# PowerSupplies.net
KiCad netlist of a schematic drawn in Altium Designer
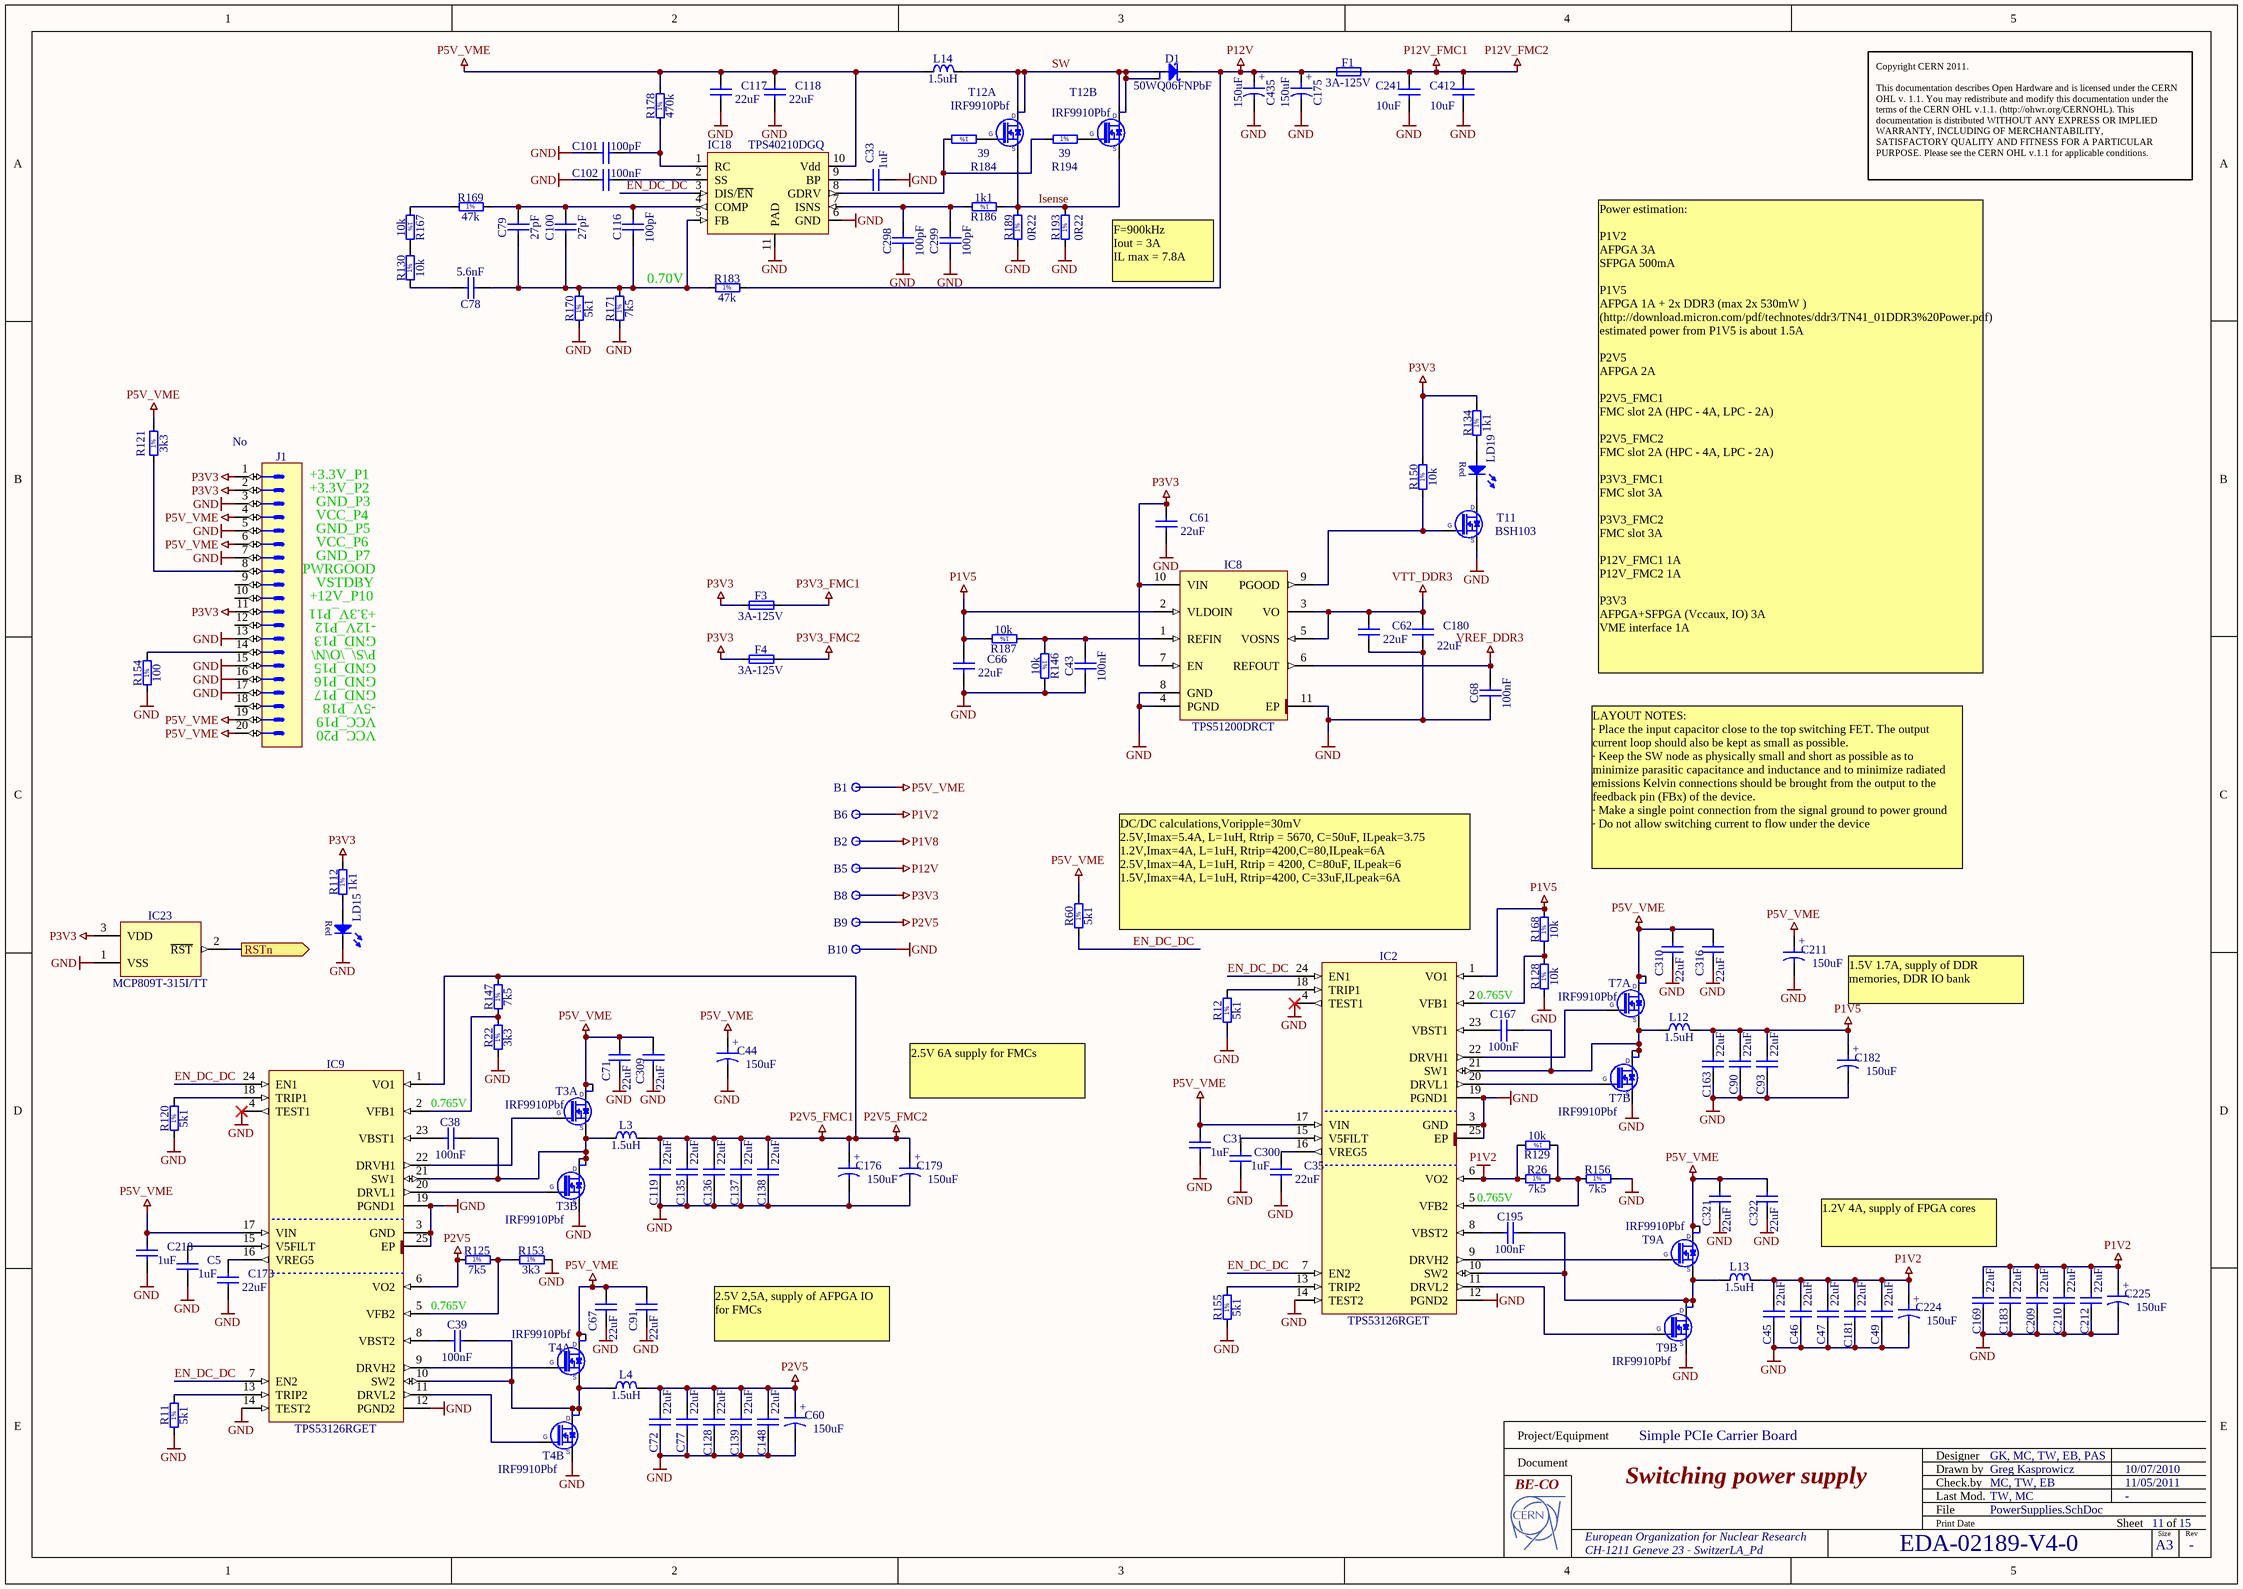
[diagram p0: PowerSupplies.SchDoc]

(export (version "E")
  (design (tool "Eeschema 10.0.6"))
  (components
    (comp (ref "B1")
      (value "Plated Hole")
      (footprint "c130h80")
      (description "Single Terminal Socket")
      (fields (field (name "PART NUMBER") "PLATED_HOLE0.8_PAD1.3") (field (name "AUTHOR") "CERN DEM JLC"))
      (libsource (lib "Eletro-mechanical") (part "Single Terminal Socket"))
    )
    (comp (ref "B2")
      (value "Plated Hole")
      (footprint "c130h80")
      (description "Single Terminal Socket")
      (fields (field (name "PART NUMBER") "PLATED_HOLE0.8_PAD1.3") (field (name "AUTHOR") "CERN DEM JLC"))
      (libsource (lib "Eletro-mechanical") (part "Single Terminal Socket"))
    )
    (comp (ref "B5")
      (value "Plated Hole")
      (footprint "c130h80")
      (description "Single Terminal Socket")
      (fields (field (name "PART NUMBER") "PLATED_HOLE0.8_PAD1.3") (field (name "AUTHOR") "CERN DEM JLC"))
      (libsource (lib "Eletro-mechanical") (part "Single Terminal Socket"))
    )
    (comp (ref "B6")
      (value "Plated Hole")
      (footprint "c130h80")
      (description "Single Terminal Socket")
      (fields (field (name "PART NUMBER") "PLATED_HOLE0.8_PAD1.3") (field (name "AUTHOR") "CERN DEM JLC"))
      (libsource (lib "Eletro-mechanical") (part "Single Terminal Socket"))
    )
    (comp (ref "B8")
      (value "Plated Hole")
      (footprint "c130h80")
      (description "Single Terminal Socket")
      (fields (field (name "PART NUMBER") "PLATED_HOLE0.8_PAD1.3") (field (name "AUTHOR") "CERN DEM JLC"))
      (libsource (lib "Eletro-mechanical") (part "Single Terminal Socket"))
    )
    (comp (ref "B9")
      (value "Plated Hole")
      (footprint "c130h80")
      (description "Single Terminal Socket")
      (fields (field (name "PART NUMBER") "PLATED_HOLE0.8_PAD1.3") (field (name "AUTHOR") "CERN DEM JLC"))
      (libsource (lib "Eletro-mechanical") (part "Single Terminal Socket"))
    )
    (comp (ref "B10")
      (value "Plated Hole")
      (footprint "c130h80")
      (description "Single Terminal Socket")
      (fields (field (name "PART NUMBER") "PLATED_HOLE0.8_PAD1.3") (field (name "AUTHOR") "CERN DEM JLC"))
      (libsource (lib "Eletro-mechanical") (part "Single Terminal Socket"))
    )
    (comp (ref "C5")
      (value "1uF")
      (footprint "CAPC1608X87N")
      (description "Non-polarised capacitor")
      (fields
        (field (name "PART NUMBER") "CC0603_1UF_16V_10%_X7R")
        (field (name "VOLTAGE") "16V")
        (field (name "AUTHOR") "CERN DEM JLC")
      )
      (libsource (lib "Capacitors") (part "Capacitor - non polarized"))
    )
    (comp (ref "C31")
      (value "1uF")
      (footprint "CAPC1608X87N")
      (description "Non-polarised capacitor")
      (fields
        (field (name "PART NUMBER") "CC0603_1UF_16V_10%_X7R")
        (field (name "VOLTAGE") "16V")
        (field (name "AUTHOR") "CERN DEM JLC")
      )
      (libsource (lib "Capacitors") (part "Capacitor - non polarized"))
    )
    (comp (ref "C33")
      (value "1uF")
      (footprint "CAPC1608X87N")
      (description "Non-polarised capacitor")
      (fields
        (field (name "PART NUMBER") "CC0603_1UF_16V_10%_X7R")
        (field (name "VOLTAGE") "16V")
        (field (name "AUTHOR") "CERN DEM JLC")
      )
      (libsource (lib "Capacitors") (part "Capacitor - non polarized"))
    )
    (comp (ref "C35")
      (value "22uF")
      (footprint "CAPC3216X180N")
      (description "Non-polarised capacitor")
      (fields
        (field (name "PART NUMBER") "CC1206_22UF_10V_10%_X7R")
        (field (name "VOLTAGE") "10V")
        (field (name "AUTHOR") "CERN DEM JLC")
      )
      (libsource (lib "Capacitors") (part "Capacitor - non polarized"))
    )
    (comp (ref "C38")
      (value "100nF")
      (footprint "CAPC1005X55N")
      (description "Non-polarised capacitor")
      (fields
        (field (name "PART NUMBER") "CC0402_100NF_16V_10%_X7R")
        (field (name "VOLTAGE") "16V")
        (field (name "AUTHOR") "CERN DEM JLC")
      )
      (libsource (lib "Capacitors") (part "Capacitor - non polarized"))
    )
    (comp (ref "C39")
      (value "100nF")
      (footprint "CAPC1005X55N")
      (description "Non-polarised capacitor")
      (fields
        (field (name "PART NUMBER") "CC0402_100NF_16V_10%_X7R")
        (field (name "VOLTAGE") "16V")
        (field (name "AUTHOR") "CERN DEM JLC")
      )
      (libsource (lib "Capacitors") (part "Capacitor - non polarized"))
    )
    (comp (ref "C43")
      (value "100nF")
      (footprint "CAPC1005X55N")
      (description "Non-polarised capacitor")
      (fields
        (field (name "PART NUMBER") "CC0402_100NF_16V_10%_X7R")
        (field (name "VOLTAGE") "16V")
        (field (name "AUTHOR") "CERN DEM JLC")
      )
      (libsource (lib "Capacitors") (part "Capacitor - non polarized"))
    )
    (comp (ref "C44")
      (value "150uF")
      (footprint "CAPPR350-850X700")
      (description "Polarised capacitor")
      (fields
        (field (name "PART NUMBER") "CAER_150UF_6.3V_20%_SANYO_6SEQP150M")
        (field (name "VOLTAGE") "6.3V")
        (field (name "AUTHOR") "CERN DEM JLC")
      )
      (libsource (lib "Capacitors") (part "Capacitor - polarized"))
    )
    (comp (ref "C45")
      (value "22uF")
      (footprint "CAPC3216X180N")
      (description "Non-polarised capacitor")
      (fields
        (field (name "PART NUMBER") "CC1206_22UF_10V_10%_X7R")
        (field (name "VOLTAGE") "10V")
        (field (name "AUTHOR") "CERN DEM JLC")
      )
      (libsource (lib "Capacitors") (part "Capacitor - non polarized"))
    )
    (comp (ref "C46")
      (value "22uF")
      (footprint "CAPC3216X180N")
      (description "Non-polarised capacitor")
      (fields
        (field (name "PART NUMBER") "CC1206_22UF_10V_10%_X7R")
        (field (name "VOLTAGE") "10V")
        (field (name "AUTHOR") "CERN DEM JLC")
      )
      (libsource (lib "Capacitors") (part "Capacitor - non polarized"))
    )
    (comp (ref "C47")
      (value "22uF")
      (footprint "CAPC3216X180N")
      (description "Non-polarised capacitor")
      (fields
        (field (name "PART NUMBER") "CC1206_22UF_10V_10%_X7R")
        (field (name "VOLTAGE") "10V")
        (field (name "AUTHOR") "CERN DEM JLC")
      )
      (libsource (lib "Capacitors") (part "Capacitor - non polarized"))
    )
    (comp (ref "C49")
      (value "22uF")
      (footprint "CAPC3216X180N")
      (description "Non-polarised capacitor")
      (fields
        (field (name "PART NUMBER") "CC1206_22UF_10V_10%_X7R")
        (field (name "VOLTAGE") "10V")
        (field (name "AUTHOR") "CERN DEM JLC")
      )
      (libsource (lib "Capacitors") (part "Capacitor - non polarized"))
    )
    (comp (ref "C60")
      (value "150uF")
      (footprint "CAPPR350-850X700")
      (description "Polarised capacitor")
      (fields
        (field (name "PART NUMBER") "CAER_150UF_6.3V_20%_SANYO_6SEQP150M")
        (field (name "VOLTAGE") "6.3V")
        (field (name "AUTHOR") "CERN DEM JLC")
      )
      (libsource (lib "Capacitors") (part "Capacitor - polarized"))
    )
    (comp (ref "C61")
      (value "22uF")
      (footprint "CAPC3216X180N")
      (description "Non-polarised capacitor")
      (fields
        (field (name "PART NUMBER") "CC1206_22UF_10V_10%_X7R")
        (field (name "VOLTAGE") "10V")
        (field (name "AUTHOR") "CERN DEM JLC")
      )
      (libsource (lib "Capacitors") (part "Capacitor - non polarized"))
    )
    (comp (ref "C62")
      (value "22uF")
      (footprint "CAPC3216X180N")
      (description "Non-polarised capacitor")
      (fields
        (field (name "PART NUMBER") "CC1206_22UF_10V_10%_X7R")
        (field (name "VOLTAGE") "10V")
        (field (name "AUTHOR") "CERN DEM JLC")
      )
      (libsource (lib "Capacitors") (part "Capacitor - non polarized"))
    )
    (comp (ref "C66")
      (value "22uF")
      (footprint "CAPC3216X180N")
      (description "Non-polarised capacitor")
      (fields
        (field (name "PART NUMBER") "CC1206_22UF_10V_10%_X7R")
        (field (name "VOLTAGE") "10V")
        (field (name "AUTHOR") "CERN DEM JLC")
      )
      (libsource (lib "Capacitors") (part "Capacitor - non polarized"))
    )
    (comp (ref "C67")
      (value "22uF")
      (footprint "CAPC3216X180N")
      (description "Non-polarised capacitor")
      (fields
        (field (name "PART NUMBER") "CC1206_22UF_10V_10%_X7R")
        (field (name "VOLTAGE") "10V")
        (field (name "AUTHOR") "CERN DEM JLC")
      )
      (libsource (lib "Capacitors") (part "Capacitor - non polarized"))
    )
    (comp (ref "C68")
      (value "100nF")
      (footprint "CAPC1005X55N")
      (description "Non-polarised capacitor")
      (fields
        (field (name "PART NUMBER") "CC0402_100NF_16V_10%_X7R")
        (field (name "VOLTAGE") "16V")
        (field (name "AUTHOR") "CERN DEM JLC")
      )
      (libsource (lib "Capacitors") (part "Capacitor - non polarized"))
    )
    (comp (ref "C71")
      (value "22uF")
      (footprint "CAPC3216X180N")
      (description "Non-polarised capacitor")
      (fields
        (field (name "PART NUMBER") "CC1206_22UF_10V_10%_X7R")
        (field (name "VOLTAGE") "10V")
        (field (name "AUTHOR") "CERN DEM JLC")
      )
      (libsource (lib "Capacitors") (part "Capacitor - non polarized"))
    )
    (comp (ref "C72")
      (value "22uF")
      (footprint "CAPC3216X180N")
      (description "Non-polarised capacitor")
      (fields
        (field (name "PART NUMBER") "CC1206_22UF_10V_10%_X7R")
        (field (name "VOLTAGE") "10V")
        (field (name "AUTHOR") "CERN DEM JLC")
      )
      (libsource (lib "Capacitors") (part "Capacitor - non polarized"))
    )
    (comp (ref "C77")
      (value "22uF")
      (footprint "CAPC3216X180N")
      (description "Non-polarised capacitor")
      (fields
        (field (name "PART NUMBER") "CC1206_22UF_10V_10%_X7R")
        (field (name "VOLTAGE") "10V")
        (field (name "AUTHOR") "CERN DEM JLC")
      )
      (libsource (lib "Capacitors") (part "Capacitor - non polarized"))
    )
    (comp (ref "C78")
      (value "5.6nF")
      (footprint "CAPC1608X87N")
      (description "Non-polarised capacitor")
      (fields
        (field (name "PART NUMBER") "CC0603_5.6NF_50V_5%_X7R")
        (field (name "VOLTAGE") "50V")
        (field (name "AUTHOR") "CERN DEM JLC")
      )
      (libsource (lib "Capacitors") (part "Capacitor - non polarized"))
    )
    (comp (ref "C79")
      (value "27pF")
      (footprint "CAPC1608X87N")
      (description "Non-polarised capacitor")
      (fields
        (field (name "PART NUMBER") "CC0603_27PF_50V_5%_NP0")
        (field (name "VOLTAGE") "50V")
        (field (name "AUTHOR") "CERN DEM JLC")
      )
      (libsource (lib "Capacitors") (part "Capacitor - non polarized"))
    )
    (comp (ref "C90")
      (value "22uF")
      (footprint "CAPC3216X180N")
      (description "Non-polarised capacitor")
      (fields
        (field (name "PART NUMBER") "CC1206_22UF_10V_10%_X7R")
        (field (name "VOLTAGE") "10V")
        (field (name "AUTHOR") "CERN DEM JLC")
      )
      (libsource (lib "Capacitors") (part "Capacitor - non polarized"))
    )
    (comp (ref "C91")
      (value "22uF")
      (footprint "CAPC3216X180N")
      (description "Non-polarised capacitor")
      (fields
        (field (name "PART NUMBER") "CC1206_22UF_10V_10%_X7R")
        (field (name "VOLTAGE") "10V")
        (field (name "AUTHOR") "CERN DEM JLC")
      )
      (libsource (lib "Capacitors") (part "Capacitor - non polarized"))
    )
    (comp (ref "C93")
      (value "22uF")
      (footprint "CAPC3216X180N")
      (description "Non-polarised capacitor")
      (fields
        (field (name "PART NUMBER") "CC1206_22UF_10V_10%_X7R")
        (field (name "VOLTAGE") "10V")
        (field (name "AUTHOR") "CERN DEM JLC")
      )
      (libsource (lib "Capacitors") (part "Capacitor - non polarized"))
    )
    (comp (ref "C100")
      (value "27pF")
      (footprint "CAPC1608X87N")
      (description "Non-polarised capacitor")
      (fields
        (field (name "PART NUMBER") "CC0603_27PF_50V_5%_NP0")
        (field (name "VOLTAGE") "50V")
        (field (name "AUTHOR") "CERN DEM JLC")
      )
      (libsource (lib "Capacitors") (part "Capacitor - non polarized"))
    )
    (comp (ref "C101")
      (value "100pF")
      (footprint "CAPC1608X87N")
      (description "Non-polarised capacitor")
      (fields
        (field (name "PART NUMBER") "CC0603_100PF_50V_5%_NP0")
        (field (name "VOLTAGE") "50V")
        (field (name "AUTHOR") "CERN DEM JLC")
      )
      (libsource (lib "Capacitors") (part "Capacitor - non polarized"))
    )
    (comp (ref "C102")
      (value "100nF")
      (footprint "CAPC1005X55N")
      (description "Non-polarised capacitor")
      (fields
        (field (name "PART NUMBER") "CC0402_100NF_16V_10%_X7R")
        (field (name "VOLTAGE") "16V")
        (field (name "AUTHOR") "CERN DEM JLC")
      )
      (libsource (lib "Capacitors") (part "Capacitor - non polarized"))
    )
    (comp (ref "C116")
      (value "100pF")
      (footprint "CAPC1608X87N")
      (description "Non-polarised capacitor")
      (fields
        (field (name "PART NUMBER") "CC0603_100PF_50V_5%_NP0")
        (field (name "VOLTAGE") "50V")
        (field (name "AUTHOR") "CERN DEM JLC")
      )
      (libsource (lib "Capacitors") (part "Capacitor - non polarized"))
    )
    (comp (ref "C117")
      (value "22uF")
      (footprint "CAPC3216X180N")
      (description "Non-polarised capacitor")
      (fields
        (field (name "PART NUMBER") "CC1206_22UF_10V_10%_X7R")
        (field (name "VOLTAGE") "10V")
        (field (name "AUTHOR") "CERN DEM JLC")
      )
      (libsource (lib "Capacitors") (part "Capacitor - non polarized"))
    )
    (comp (ref "C118")
      (value "22uF")
      (footprint "CAPC3216X180N")
      (description "Non-polarised capacitor")
      (fields
        (field (name "PART NUMBER") "CC1206_22UF_10V_10%_X7R")
        (field (name "VOLTAGE") "10V")
        (field (name "AUTHOR") "CERN DEM JLC")
      )
      (libsource (lib "Capacitors") (part "Capacitor - non polarized"))
    )
    (comp (ref "C119")
      (value "22uF")
      (footprint "CAPC3216X180N")
      (description "Non-polarised capacitor")
      (fields
        (field (name "PART NUMBER") "CC1206_22UF_10V_10%_X7R")
        (field (name "VOLTAGE") "10V")
        (field (name "AUTHOR") "CERN DEM JLC")
      )
      (libsource (lib "Capacitors") (part "Capacitor - non polarized"))
    )
    (comp (ref "C128")
      (value "22uF")
      (footprint "CAPC3216X180N")
      (description "Non-polarised capacitor")
      (fields
        (field (name "PART NUMBER") "CC1206_22UF_10V_10%_X7R")
        (field (name "VOLTAGE") "10V")
        (field (name "AUTHOR") "CERN DEM JLC")
      )
      (libsource (lib "Capacitors") (part "Capacitor - non polarized"))
    )
    (comp (ref "C135")
      (value "22uF")
      (footprint "CAPC3216X180N")
      (description "Non-polarised capacitor")
      (fields
        (field (name "PART NUMBER") "CC1206_22UF_10V_10%_X7R")
        (field (name "VOLTAGE") "10V")
        (field (name "AUTHOR") "CERN DEM JLC")
      )
      (libsource (lib "Capacitors") (part "Capacitor - non polarized"))
    )
    (comp (ref "C136")
      (value "22uF")
      (footprint "CAPC3216X180N")
      (description "Non-polarised capacitor")
      (fields
        (field (name "PART NUMBER") "CC1206_22UF_10V_10%_X7R")
        (field (name "VOLTAGE") "10V")
        (field (name "AUTHOR") "CERN DEM JLC")
      )
      (libsource (lib "Capacitors") (part "Capacitor - non polarized"))
    )
    (comp (ref "C137")
      (value "22uF")
      (footprint "CAPC3216X180N")
      (description "Non-polarised capacitor")
      (fields
        (field (name "PART NUMBER") "CC1206_22UF_10V_10%_X7R")
        (field (name "VOLTAGE") "10V")
        (field (name "AUTHOR") "CERN DEM JLC")
      )
      (libsource (lib "Capacitors") (part "Capacitor - non polarized"))
    )
    (comp (ref "C138")
      (value "22uF")
      (footprint "CAPC3216X180N")
      (description "Non-polarised capacitor")
      (fields
        (field (name "PART NUMBER") "CC1206_22UF_10V_10%_X7R")
        (field (name "VOLTAGE") "10V")
        (field (name "AUTHOR") "CERN DEM JLC")
      )
      (libsource (lib "Capacitors") (part "Capacitor - non polarized"))
    )
    (comp (ref "C139")
      (value "22uF")
      (footprint "CAPC3216X180N")
      (description "Non-polarised capacitor")
      (fields
        (field (name "PART NUMBER") "CC1206_22UF_10V_10%_X7R")
        (field (name "VOLTAGE") "10V")
        (field (name "AUTHOR") "CERN DEM JLC")
      )
      (libsource (lib "Capacitors") (part "Capacitor - non polarized"))
    )
    (comp (ref "C148")
      (value "22uF")
      (footprint "CAPC3216X180N")
      (description "Non-polarised capacitor")
      (fields
        (field (name "PART NUMBER") "CC1206_22UF_10V_10%_X7R")
        (field (name "VOLTAGE") "10V")
        (field (name "AUTHOR") "CERN DEM JLC")
      )
      (libsource (lib "Capacitors") (part "Capacitor - non polarized"))
    )
    (comp (ref "C163")
      (value "22uF")
      (footprint "CAPC3216X180N")
      (description "Non-polarised capacitor")
      (fields
        (field (name "PART NUMBER") "CC1206_22UF_10V_10%_X7R")
        (field (name "VOLTAGE") "10V")
        (field (name "AUTHOR") "CERN DEM JLC")
      )
      (libsource (lib "Capacitors") (part "Capacitor - non polarized"))
    )
    (comp (ref "C167")
      (value "100nF")
      (footprint "CAPC1005X55N")
      (description "Non-polarised capacitor")
      (fields
        (field (name "PART NUMBER") "CC0402_100NF_16V_10%_X7R")
        (field (name "VOLTAGE") "16V")
        (field (name "AUTHOR") "CERN DEM JLC")
      )
      (libsource (lib "Capacitors") (part "Capacitor - non polarized"))
    )
    (comp (ref "C169")
      (value "22uF")
      (footprint "CAPC3216X180N")
      (description "Non-polarised capacitor")
      (fields
        (field (name "PART NUMBER") "CC1206_22UF_10V_10%_X7R")
        (field (name "VOLTAGE") "10V")
        (field (name "AUTHOR") "CERN DEM JLC")
      )
      (libsource (lib "Capacitors") (part "Capacitor - non polarized"))
    )
    (comp (ref "C173")
      (value "22uF")
      (footprint "CAPC3216X180N")
      (description "Non-polarised capacitor")
      (fields
        (field (name "PART NUMBER") "CC1206_22UF_10V_10%_X7R")
        (field (name "VOLTAGE") "10V")
        (field (name "AUTHOR") "CERN DEM JLC")
      )
      (libsource (lib "Capacitors") (part "Capacitor - non polarized"))
    )
    (comp (ref "C175")
      (value "150uF")
      (footprint "CAPPR500-1050X800")
      (description "Polarised capacitor")
      (fields
        (field (name "PART NUMBER") "CAER_150UF_16V_20%_SANYO_16SEQP150M")
        (field (name "VOLTAGE") "16V")
        (field (name "AUTHOR") "CERN DEM JLC")
      )
      (libsource (lib "Capacitors") (part "Capacitor - polarized"))
    )
    (comp (ref "C176")
      (value "150uF")
      (footprint "CAPPR350-850X700")
      (description "Polarised capacitor")
      (fields
        (field (name "PART NUMBER") "CAER_150UF_6.3V_20%_SANYO_6SEQP150M")
        (field (name "VOLTAGE") "6.3V")
        (field (name "AUTHOR") "CERN DEM JLC")
      )
      (libsource (lib "Capacitors") (part "Capacitor - polarized"))
    )
    (comp (ref "C179")
      (value "150uF")
      (footprint "CAPPR350-850X700")
      (description "Polarised capacitor")
      (fields
        (field (name "PART NUMBER") "CAER_150UF_6.3V_20%_SANYO_6SEQP150M")
        (field (name "VOLTAGE") "6.3V")
        (field (name "AUTHOR") "CERN DEM JLC")
      )
      (libsource (lib "Capacitors") (part "Capacitor - polarized"))
    )
    (comp (ref "C180")
      (value "22uF")
      (footprint "CAPC3216X180N")
      (description "Non-polarised capacitor")
      (fields
        (field (name "PART NUMBER") "CC1206_22UF_10V_10%_X7R")
        (field (name "VOLTAGE") "10V")
        (field (name "AUTHOR") "CERN DEM JLC")
      )
      (libsource (lib "Capacitors") (part "Capacitor - non polarized"))
    )
    (comp (ref "C181")
      (value "22uF")
      (footprint "CAPC3216X180N")
      (description "Non-polarised capacitor")
      (fields
        (field (name "PART NUMBER") "CC1206_22UF_10V_10%_X7R")
        (field (name "VOLTAGE") "10V")
        (field (name "AUTHOR") "CERN DEM JLC")
      )
      (libsource (lib "Capacitors") (part "Capacitor - non polarized"))
    )
    (comp (ref "C182")
      (value "150uF")
      (footprint "CAPPR350-850X700")
      (description "Polarised capacitor")
      (fields
        (field (name "PART NUMBER") "CAER_150UF_6.3V_20%_SANYO_6SEQP150M")
        (field (name "VOLTAGE") "6.3V")
        (field (name "AUTHOR") "CERN DEM JLC")
      )
      (libsource (lib "Capacitors") (part "Capacitor - polarized"))
    )
    (comp (ref "C183")
      (value "22uF")
      (footprint "CAPC3216X180N")
      (description "Non-polarised capacitor")
      (fields
        (field (name "PART NUMBER") "CC1206_22UF_10V_10%_X7R")
        (field (name "VOLTAGE") "10V")
        (field (name "AUTHOR") "CERN DEM JLC")
      )
      (libsource (lib "Capacitors") (part "Capacitor - non polarized"))
    )
    (comp (ref "C195")
      (value "100nF")
      (footprint "CAPC1005X55N")
      (description "Non-polarised capacitor")
      (fields
        (field (name "PART NUMBER") "CC0402_100NF_16V_10%_X7R")
        (field (name "VOLTAGE") "16V")
        (field (name "AUTHOR") "CERN DEM JLC")
      )
      (libsource (lib "Capacitors") (part "Capacitor - non polarized"))
    )
    (comp (ref "C209")
      (value "22uF")
      (footprint "CAPC3216X180N")
      (description "Non-polarised capacitor")
      (fields
        (field (name "PART NUMBER") "CC1206_22UF_10V_10%_X7R")
        (field (name "VOLTAGE") "10V")
        (field (name "AUTHOR") "CERN DEM JLC")
      )
      (libsource (lib "Capacitors") (part "Capacitor - non polarized"))
    )
    (comp (ref "C210")
      (value "22uF")
      (footprint "CAPC3216X180N")
      (description "Non-polarised capacitor")
      (fields
        (field (name "PART NUMBER") "CC1206_22UF_10V_10%_X7R")
        (field (name "VOLTAGE") "10V")
        (field (name "AUTHOR") "CERN DEM JLC")
      )
      (libsource (lib "Capacitors") (part "Capacitor - non polarized"))
    )
    (comp (ref "C211")
      (value "150uF")
      (footprint "CAPPR350-850X700")
      (description "Polarised capacitor")
      (fields
        (field (name "PART NUMBER") "CAER_150UF_6.3V_20%_SANYO_6SEQP150M")
        (field (name "VOLTAGE") "6.3V")
        (field (name "AUTHOR") "CERN DEM JLC")
      )
      (libsource (lib "Capacitors") (part "Capacitor - polarized"))
    )
    (comp (ref "C212")
      (value "22uF")
      (footprint "CAPC3216X180N")
      (description "Non-polarised capacitor")
      (fields
        (field (name "PART NUMBER") "CC1206_22UF_10V_10%_X7R")
        (field (name "VOLTAGE") "10V")
        (field (name "AUTHOR") "CERN DEM JLC")
      )
      (libsource (lib "Capacitors") (part "Capacitor - non polarized"))
    )
    (comp (ref "C218")
      (value "1uF")
      (footprint "CAPC1608X87N")
      (description "Non-polarised capacitor")
      (fields
        (field (name "PART NUMBER") "CC0603_1UF_16V_10%_X7R")
        (field (name "VOLTAGE") "16V")
        (field (name "AUTHOR") "CERN DEM JLC")
      )
      (libsource (lib "Capacitors") (part "Capacitor - non polarized"))
    )
    (comp (ref "C224")
      (value "150uF")
      (footprint "CAPPR350-850X700")
      (description "Polarised capacitor")
      (fields
        (field (name "PART NUMBER") "CAER_150UF_6.3V_20%_SANYO_6SEQP150M")
        (field (name "VOLTAGE") "6.3V")
        (field (name "AUTHOR") "CERN DEM JLC")
      )
      (libsource (lib "Capacitors") (part "Capacitor - polarized"))
    )
    (comp (ref "C225")
      (value "150uF")
      (footprint "CAPPR350-850X700")
      (description "Polarised capacitor")
      (fields
        (field (name "PART NUMBER") "CAER_150UF_6.3V_20%_SANYO_6SEQP150M")
        (field (name "VOLTAGE") "6.3V")
        (field (name "AUTHOR") "CERN DEM JLC")
      )
      (libsource (lib "Capacitors") (part "Capacitor - polarized"))
    )
    (comp (ref "C241")
      (value "10uF")
      (footprint "CAPC3225X270N")
      (description "Non-polarised capacitor")
      (fields
        (field (name "PART NUMBER") "CC1210_10UF_25V_10%_X7R")
        (field (name "VOLTAGE") "25V")
        (field (name "AUTHOR") "CERN DEM JLC")
      )
      (libsource (lib "Capacitors") (part "Capacitor - non polarized"))
    )
    (comp (ref "C298")
      (value "100pF")
      (footprint "CAPC1608X87N")
      (description "Non-polarised capacitor")
      (fields
        (field (name "PART NUMBER") "CC0603_100PF_50V_5%_NP0")
        (field (name "VOLTAGE") "50V")
        (field (name "AUTHOR") "CERN DEM JLC")
      )
      (libsource (lib "Capacitors") (part "Capacitor - non polarized"))
    )
    (comp (ref "C299")
      (value "100pF")
      (footprint "CAPC1608X87N")
      (description "Non-polarised capacitor")
      (fields
        (field (name "PART NUMBER") "CC0603_100PF_50V_5%_NP0")
        (field (name "VOLTAGE") "50V")
        (field (name "AUTHOR") "CERN DEM JLC")
      )
      (libsource (lib "Capacitors") (part "Capacitor - non polarized"))
    )
    (comp (ref "C300")
      (value "1uF")
      (footprint "CAPC1608X87N")
      (description "Non-polarised capacitor")
      (fields
        (field (name "PART NUMBER") "CC0603_1UF_16V_10%_X7R")
        (field (name "VOLTAGE") "16V")
        (field (name "AUTHOR") "CERN DEM JLC")
      )
      (libsource (lib "Capacitors") (part "Capacitor - non polarized"))
    )
    (comp (ref "C309")
      (value "22uF")
      (footprint "CAPC3216X180N")
      (description "Non-polarised capacitor")
      (fields
        (field (name "PART NUMBER") "CC1206_22UF_10V_10%_X7R")
        (field (name "VOLTAGE") "10V")
        (field (name "AUTHOR") "CERN DEM JLC")
      )
      (libsource (lib "Capacitors") (part "Capacitor - non polarized"))
    )
    (comp (ref "C310")
      (value "22uF")
      (footprint "CAPC3216X180N")
      (description "Non-polarised capacitor")
      (fields
        (field (name "PART NUMBER") "CC1206_22UF_10V_10%_X7R")
        (field (name "VOLTAGE") "10V")
        (field (name "AUTHOR") "CERN DEM JLC")
      )
      (libsource (lib "Capacitors") (part "Capacitor - non polarized"))
    )
    (comp (ref "C316")
      (value "22uF")
      (footprint "CAPC3216X180N")
      (description "Non-polarised capacitor")
      (fields
        (field (name "PART NUMBER") "CC1206_22UF_10V_10%_X7R")
        (field (name "VOLTAGE") "10V")
        (field (name "AUTHOR") "CERN DEM JLC")
      )
      (libsource (lib "Capacitors") (part "Capacitor - non polarized"))
    )
    (comp (ref "C321")
      (value "22uF")
      (footprint "CAPC3216X180N")
      (description "Non-polarised capacitor")
      (fields
        (field (name "PART NUMBER") "CC1206_22UF_10V_10%_X7R")
        (field (name "VOLTAGE") "10V")
        (field (name "AUTHOR") "CERN DEM JLC")
      )
      (libsource (lib "Capacitors") (part "Capacitor - non polarized"))
    )
    (comp (ref "C322")
      (value "22uF")
      (footprint "CAPC3216X180N")
      (description "Non-polarised capacitor")
      (fields
        (field (name "PART NUMBER") "CC1206_22UF_10V_10%_X7R")
        (field (name "VOLTAGE") "10V")
        (field (name "AUTHOR") "CERN DEM JLC")
      )
      (libsource (lib "Capacitors") (part "Capacitor - non polarized"))
    )
    (comp (ref "C412")
      (value "10uF")
      (footprint "CAPC3225X270N")
      (description "Non-polarised capacitor")
      (fields
        (field (name "PART NUMBER") "CC1210_10UF_25V_10%_X7R")
        (field (name "VOLTAGE") "25V")
        (field (name "AUTHOR") "CERN DEM JLC")
      )
      (libsource (lib "Capacitors") (part "Capacitor - non polarized"))
    )
    (comp (ref "C435")
      (value "150uF")
      (footprint "CAPPR500-1050X800")
      (description "Polarised capacitor")
      (fields
        (field (name "PART NUMBER") "CAER_150UF_16V_20%_SANYO_16SEQP150M")
        (field (name "VOLTAGE") "16V")
        (field (name "AUTHOR") "CERN DEM JLC")
      )
      (libsource (lib "Capacitors") (part "Capacitor - polarized"))
    )
    (comp (ref "D1")
      (value "50WQ06FNPbF")
      (footprint "TO228P991X239-3N-R546X521")
      (description "Diode  Schottky Anode pin 1 and 2 cathode pin 3")
      (fields
        (field (name "VOLTAGE") "60V")
        (field (name "POWER") "5.5A")
        (field (name "AUTHOR") "CERN DEM JLC")
      )
      (libsource (lib "ICs And Semiconductors") (part "Diode Schottky A1A2_C3"))
    )
    (comp (ref "F1")
      (value "3A-125V")
      (footprint "FUSE_LITTELFUSE_0154")
      (description "Fuse")
      (fields
        (field (name "PART NUMBER") "FUSE_LITTELFUSE_0154003.DR")
        (field (name "MANUFACTURER") "LITTELFUSE")
        (field (name "AUTHOR") "CERN DEM JMW")
      )
      (libsource (lib "Eletro-mechanical") (part "Fuse"))
    )
    (comp (ref "F3")
      (value "3A-125V")
      (footprint "FUSE_LITTELFUSE_0154")
      (description "Fuse")
      (fields
        (field (name "PART NUMBER") "FUSE_LITTELFUSE_0154003.DR")
        (field (name "MANUFACTURER") "LITTELFUSE")
        (field (name "AUTHOR") "CERN DEM JMW")
      )
      (libsource (lib "Eletro-mechanical") (part "Fuse"))
    )
    (comp (ref "F4")
      (value "3A-125V")
      (footprint "FUSE_LITTELFUSE_0154")
      (description "Fuse")
      (fields
        (field (name "PART NUMBER") "FUSE_LITTELFUSE_0154003.DR")
        (field (name "MANUFACTURER") "LITTELFUSE")
        (field (name "AUTHOR") "CERN DEM JMW")
      )
      (libsource (lib "Eletro-mechanical") (part "Fuse"))
    )
    (comp (ref "IC2")
      (value "TPS53126RGET")
      (footprint "QFN50P400X400X100-25N-S255")
      (description "Dual Synchronous Step-Down Controller For Low Voltage Power Rails")
      (fields (field (name "MANUFACTURER") "TEXAS INSTRUMENTS") (field (name "AUTHOR") "CERN DEM JLC"))
      (libsource (lib "ICs And Semiconductors") (part "TPS53126RGET"))
    )
    (comp (ref "IC8")
      (value "TPS51200DRCT")
      (footprint "SON50P300X300X100-11N-R175X250")
      (description "Sink/Source DDR Termination Regulator")
      (fields (field (name "MANUFACTURER") "TEXAS INSTRUMENTS") (field (name "AUTHOR") "CERN DEM JLC"))
      (libsource (lib "ICs And Semiconductors") (part "TPS51200DRC"))
    )
    (comp (ref "IC9")
      (value "TPS53126RGET")
      (footprint "QFN50P400X400X100-25N-S255")
      (description "Dual Synchronous Step-Down Controller For Low Voltage Power Rails")
      (fields (field (name "MANUFACTURER") "TEXAS INSTRUMENTS") (field (name "AUTHOR") "CERN DEM JLC"))
      (libsource (lib "ICs And Semiconductors") (part "TPS53126RGET"))
    )
    (comp (ref "IC18")
      (value "TPS40210DGQ")
      (footprint "MSOP10_thermal")
      (description "4.5-V TO 52-V CURRENT MODE BOOST CONTROLLER")
      (libsource (lib "LIBRARY_SCH") (part "PM_TPS40210"))
    )
    (comp (ref "IC23")
      (value "MCP809T-315I/TT")
      (footprint "SOT95P237X112-3N")
      (description "3.075V Microcontroller Supervisory Circuit With Push-Pull Output")
      (fields (field (name "MANUFACTURER") "MICROCHIP TECHNOLOGY") (field (name "AUTHOR") "CERN DEM JLC"))
      (libsource (lib "ICs And Semiconductors") (part "MCP809"))
    )
    (comp (ref "J1")
      (value "Mini-Fit Jr.™")
      (footprint "MOLEX_39-28-1203")
      (description "Connector 20 Male")
      (fields
        (field (name "PART NUMBER") "MOLEX_39-28-1203")
        (field (name "MOUNTED") "No")
        (field (name "MANUFACTURER") "MOLEX")
        (field (name "AUTHOR") "CERN DEM JLC")
      )
      (libsource (lib "Connectors") (part "Connector 20 Male"))
    )
    (comp (ref "L3")
      (value "1.5uH")
      (footprint "IND_BOURNS_SRR1260")
      (description "Inductor")
      (fields
        (field (name "PART NUMBER") "IND_1.5UH_30%_BOURNS_SRR1260")
        (field (name "POWER") "8.8A")
        (field (name "AUTHOR") "CERN DEM JLC")
      )
      (libsource (lib "Inductors & Transformers") (part "Inductor"))
    )
    (comp (ref "L4")
      (value "1.5uH")
      (footprint "IND_BOURNS_SRR1260")
      (description "Inductor")
      (fields
        (field (name "PART NUMBER") "IND_1.5UH_30%_BOURNS_SRR1260")
        (field (name "POWER") "8.8A")
        (field (name "AUTHOR") "CERN DEM JLC")
      )
      (libsource (lib "Inductors & Transformers") (part "Inductor"))
    )
    (comp (ref "L12")
      (value "1.5uH")
      (footprint "IND_BOURNS_SRR1260")
      (description "Inductor")
      (fields
        (field (name "PART NUMBER") "IND_1.5UH_30%_BOURNS_SRR1260")
        (field (name "POWER") "8.8A")
        (field (name "AUTHOR") "CERN DEM JLC")
      )
      (libsource (lib "Inductors & Transformers") (part "Inductor"))
    )
    (comp (ref "L13")
      (value "1.5uH")
      (footprint "IND_BOURNS_SRR1260")
      (description "Inductor")
      (fields
        (field (name "PART NUMBER") "IND_1.5UH_30%_BOURNS_SRR1260")
        (field (name "POWER") "8.8A")
        (field (name "AUTHOR") "CERN DEM JLC")
      )
      (libsource (lib "Inductors & Transformers") (part "Inductor"))
    )
    (comp (ref "L14")
      (value "1.5uH")
      (footprint "IND_BOURNS_SRR1260")
      (description "Inductor")
      (fields
        (field (name "PART NUMBER") "IND_1.5UH_30%_BOURNS_SRR1260")
        (field (name "POWER") "8.8A")
        (field (name "AUTHOR") "CERN DEM JLC")
      )
      (libsource (lib "Inductors & Transformers") (part "Inductor"))
    )
    (comp (ref "LD15")
      (value "Red")
      (footprint "LEDC1608X80N_RED")
      (description "LED Red 1C 2A")
      (fields
        (field (name "PART NUMBER") "LED_ROHM_SML-311UTT86K")
        (field (name "MANUFACTURER") "ROHM")
        (field (name "AUTHOR") "CERN DEM JLC")
      )
      (libsource (lib "ICs And Semiconductors") (part "LED Red 1C 2A"))
    )
    (comp (ref "LD19")
      (value "Red")
      (footprint "LEDC1608X80N_RED")
      (description "LED Red 1C 2A")
      (fields
        (field (name "PART NUMBER") "LED_ROHM_SML-311UTT86K")
        (field (name "MANUFACTURER") "ROHM")
        (field (name "AUTHOR") "CERN DEM JLC")
      )
      (libsource (lib "ICs And Semiconductors") (part "LED Red 1C 2A"))
    )
    (comp (ref "R11")
      (value "5k1")
      (footprint "RESC1608X55N")
      (description "Resistor - 1%")
      (fields
        (field (name "PART NUMBER") "R0603_5K1_1%_0.1W_100PPM")
        (field (name "POWER") "0.1W")
        (field (name "AUTHOR") "CERN DEM JLC")
      )
      (libsource (lib "Resistors") (part "Resistor - 1%"))
    )
    (comp (ref "R12")
      (value "5k1")
      (footprint "RESC1608X55N")
      (description "Resistor - 1%")
      (fields
        (field (name "PART NUMBER") "R0603_5K1_1%_0.1W_100PPM")
        (field (name "POWER") "0.1W")
        (field (name "AUTHOR") "CERN DEM JLC")
      )
      (libsource (lib "Resistors") (part "Resistor - 1%"))
    )
    (comp (ref "R22")
      (value "3k3")
      (footprint "RESC1608X55N")
      (description "Resistor - 1%")
      (fields
        (field (name "PART NUMBER") "R0603_3K3_1%_0.1W_100PPM")
        (field (name "POWER") "0.1W")
        (field (name "AUTHOR") "CERN DEM JLC")
      )
      (libsource (lib "Resistors") (part "Resistor - 1%"))
    )
    (comp (ref "R26")
      (value "7k5")
      (footprint "RESC1608X55N")
      (description "Resistor - 1%")
      (fields
        (field (name "PART NUMBER") "R0603_7K5_1%_0.1W_100PPM")
        (field (name "POWER") "0.1W")
        (field (name "AUTHOR") "CERN DEM JLC")
      )
      (libsource (lib "Resistors") (part "Resistor - 1%"))
    )
    (comp (ref "R60")
      (value "5k1")
      (footprint "RESC1608X55N")
      (description "Resistor - 1%")
      (fields
        (field (name "PART NUMBER") "R0603_5K1_1%_0.1W_100PPM")
        (field (name "POWER") "0.1W")
        (field (name "AUTHOR") "CERN DEM JLC")
      )
      (libsource (lib "Resistors") (part "Resistor - 1%"))
    )
    (comp (ref "R112")
      (value "1k1")
      (footprint "RESC1608X55N")
      (description "Resistor - 1%")
      (fields
        (field (name "PART NUMBER") "R0603_1K1_1%_0.1W_100PPM")
        (field (name "POWER") "0.1W")
        (field (name "AUTHOR") "CERN DEM JLC")
      )
      (libsource (lib "Resistors") (part "Resistor - 1%"))
    )
    (comp (ref "R120")
      (value "5k1")
      (footprint "RESC1608X55N")
      (description "Resistor - 1%")
      (fields
        (field (name "PART NUMBER") "R0603_5K1_1%_0.1W_100PPM")
        (field (name "POWER") "0.1W")
        (field (name "AUTHOR") "CERN DEM JLC")
      )
      (libsource (lib "Resistors") (part "Resistor - 1%"))
    )
    (comp (ref "R121")
      (value "3k3")
      (footprint "RESC1608X55N")
      (description "Resistor - 1%")
      (fields
        (field (name "PART NUMBER") "R0603_3K3_1%_0.1W_100PPM")
        (field (name "POWER") "0.1W")
        (field (name "AUTHOR") "CERN DEM JLC")
      )
      (libsource (lib "Resistors") (part "Resistor - 1%"))
    )
    (comp (ref "R125")
      (value "7k5")
      (footprint "RESC1608X55N")
      (description "Resistor - 1%")
      (fields
        (field (name "PART NUMBER") "R0603_7K5_1%_0.1W_100PPM")
        (field (name "POWER") "0.1W")
        (field (name "AUTHOR") "CERN DEM JLC")
      )
      (libsource (lib "Resistors") (part "Resistor - 1%"))
    )
    (comp (ref "R128")
      (value "10k")
      (footprint "RESC1608X55N")
      (description "Resistor - 1%")
      (fields
        (field (name "PART NUMBER") "R0603_10K_1%_0.1W_100PPM")
        (field (name "POWER") "0.1W")
        (field (name "AUTHOR") "CERN DEM JLC")
      )
      (libsource (lib "Resistors") (part "Resistor - 1%"))
    )
    (comp (ref "R129")
      (value "10k")
      (footprint "RESC1608X55N")
      (description "Resistor - 1%")
      (fields
        (field (name "PART NUMBER") "R0603_10K_1%_0.1W_100PPM")
        (field (name "POWER") "0.1W")
        (field (name "AUTHOR") "CERN DEM JLC")
      )
      (libsource (lib "Resistors") (part "Resistor - 1%"))
    )
    (comp (ref "R130")
      (value "10k")
      (footprint "RESC1608X55N")
      (description "Resistor - 1%")
      (fields
        (field (name "PART NUMBER") "R0603_10K_1%_0.1W_100PPM")
        (field (name "POWER") "0.1W")
        (field (name "AUTHOR") "CERN DEM JLC")
      )
      (libsource (lib "Resistors") (part "Resistor - 1%"))
    )
    (comp (ref "R134")
      (value "1k1")
      (footprint "RESC1608X55N")
      (description "Resistor - 1%")
      (fields
        (field (name "PART NUMBER") "R0603_1K1_1%_0.1W_100PPM")
        (field (name "POWER") "0.1W")
        (field (name "AUTHOR") "CERN DEM JLC")
      )
      (libsource (lib "Resistors") (part "Resistor - 1%"))
    )
    (comp (ref "R146")
      (value "10k")
      (footprint "RESC1608X55N")
      (description "Resistor - 1%")
      (fields
        (field (name "PART NUMBER") "R0603_10K_1%_0.1W_100PPM")
        (field (name "POWER") "0.1W")
        (field (name "AUTHOR") "CERN DEM JLC")
      )
      (libsource (lib "Resistors") (part "Resistor - 1%"))
    )
    (comp (ref "R147")
      (value "7k5")
      (footprint "RESC1608X55N")
      (description "Resistor - 1%")
      (fields
        (field (name "PART NUMBER") "R0603_7K5_1%_0.1W_100PPM")
        (field (name "POWER") "0.1W")
        (field (name "AUTHOR") "CERN DEM JLC")
      )
      (libsource (lib "Resistors") (part "Resistor - 1%"))
    )
    (comp (ref "R150")
      (value "10k")
      (footprint "RESC1608X55N")
      (description "Resistor - 1%")
      (fields
        (field (name "PART NUMBER") "R0603_10K_1%_0.1W_100PPM")
        (field (name "POWER") "0.1W")
        (field (name "AUTHOR") "CERN DEM JLC")
      )
      (libsource (lib "Resistors") (part "Resistor - 1%"))
    )
    (comp (ref "R153")
      (value "3k3")
      (footprint "RESC1608X55N")
      (description "Resistor - 1%")
      (fields
        (field (name "PART NUMBER") "R0603_3K3_1%_0.1W_100PPM")
        (field (name "POWER") "0.1W")
        (field (name "AUTHOR") "CERN DEM JLC")
      )
      (libsource (lib "Resistors") (part "Resistor - 1%"))
    )
    (comp (ref "R154")
      (value "100")
      (footprint "RESC1608X55N")
      (description "Resistor - 1%")
      (fields
        (field (name "PART NUMBER") "R0603_100R_1%_0.1W_100PPM")
        (field (name "POWER") "0.1W")
        (field (name "AUTHOR") "CERN DEM JLC")
      )
      (libsource (lib "Resistors") (part "Resistor - 1%"))
    )
    (comp (ref "R155")
      (value "5k1")
      (footprint "RESC1608X55N")
      (description "Resistor - 1%")
      (fields
        (field (name "PART NUMBER") "R0603_5K1_1%_0.1W_100PPM")
        (field (name "POWER") "0.1W")
        (field (name "AUTHOR") "CERN DEM JLC")
      )
      (libsource (lib "Resistors") (part "Resistor - 1%"))
    )
    (comp (ref "R156")
      (value "7k5")
      (footprint "RESC1608X55N")
      (description "Resistor - 1%")
      (fields
        (field (name "PART NUMBER") "R0603_7K5_1%_0.1W_100PPM")
        (field (name "POWER") "0.1W")
        (field (name "AUTHOR") "CERN DEM JLC")
      )
      (libsource (lib "Resistors") (part "Resistor - 1%"))
    )
    (comp (ref "R167")
      (value "10k")
      (footprint "RESC1608X55N")
      (description "Resistor - 1%")
      (fields
        (field (name "PART NUMBER") "R0603_10K_1%_0.1W_100PPM")
        (field (name "POWER") "0.1W")
        (field (name "AUTHOR") "CERN DEM JLC")
      )
      (libsource (lib "Resistors") (part "Resistor - 1%"))
    )
    (comp (ref "R168")
      (value "10k")
      (footprint "RESC1608X55N")
      (description "Resistor - 1%")
      (fields
        (field (name "PART NUMBER") "R0603_10K_1%_0.1W_100PPM")
        (field (name "POWER") "0.1W")
        (field (name "AUTHOR") "CERN DEM JLC")
      )
      (libsource (lib "Resistors") (part "Resistor - 1%"))
    )
    (comp (ref "R169")
      (value "47k")
      (footprint "RESC1608X55N")
      (description "Resistor - 1%")
      (fields
        (field (name "PART NUMBER") "R0603_47K_1%_0.1W_100PPM")
        (field (name "POWER") "0.1W")
        (field (name "AUTHOR") "CERN DEM JLC")
      )
      (libsource (lib "Resistors") (part "Resistor - 1%"))
    )
    (comp (ref "R170")
      (value "5k1")
      (footprint "RESC1608X55N")
      (description "Resistor - 1%")
      (fields
        (field (name "PART NUMBER") "R0603_5K1_1%_0.1W_100PPM")
        (field (name "POWER") "0.1W")
        (field (name "AUTHOR") "CERN DEM JLC")
      )
      (libsource (lib "Resistors") (part "Resistor - 1%"))
    )
    (comp (ref "R171")
      (value "7k5")
      (footprint "RESC1608X55N")
      (description "Resistor - 1%")
      (fields
        (field (name "PART NUMBER") "R0603_7K5_1%_0.1W_100PPM")
        (field (name "POWER") "0.1W")
        (field (name "AUTHOR") "CERN DEM JLC")
      )
      (libsource (lib "Resistors") (part "Resistor - 1%"))
    )
    (comp (ref "R178")
      (value "470k")
      (footprint "RESC1608X55N")
      (description "Resistor - 1%")
      (fields
        (field (name "PART NUMBER") "R0603_470K_1%_0.1W_100PPM")
        (field (name "POWER") "0.1W")
        (field (name "AUTHOR") "CERN DEM JLC")
      )
      (libsource (lib "Resistors") (part "Resistor - 1%"))
    )
    (comp (ref "R183")
      (value "47k")
      (footprint "RESC1608X55N")
      (description "Resistor - 1%")
      (fields
        (field (name "PART NUMBER") "R0603_47K_1%_0.1W_100PPM")
        (field (name "POWER") "0.1W")
        (field (name "AUTHOR") "CERN DEM JLC")
      )
      (libsource (lib "Resistors") (part "Resistor - 1%"))
    )
    (comp (ref "R184")
      (value "39")
      (footprint "RESC1608X55N")
      (description "Resistor - 1%")
      (fields
        (field (name "PART NUMBER") "R0603_39R_1%_0.1W_100PPM")
        (field (name "POWER") "0.1W")
        (field (name "AUTHOR") "CERN DEM JLC")
      )
      (libsource (lib "Resistors") (part "Resistor - 1%"))
    )
    (comp (ref "R186")
      (value "1k1")
      (footprint "RESC1608X55N")
      (description "Resistor - 1%")
      (fields
        (field (name "PART NUMBER") "R0603_1K1_1%_0.1W_100PPM")
        (field (name "POWER") "0.1W")
        (field (name "AUTHOR") "CERN DEM JLC")
      )
      (libsource (lib "Resistors") (part "Resistor - 1%"))
    )
    (comp (ref "R187")
      (value "10k")
      (footprint "RESC1608X55N")
      (description "Resistor - 1%")
      (fields
        (field (name "PART NUMBER") "R0603_10K_1%_0.1W_100PPM")
        (field (name "POWER") "0.1W")
        (field (name "AUTHOR") "CERN DEM JLC")
      )
      (libsource (lib "Resistors") (part "Resistor - 1%"))
    )
    (comp (ref "R189")
      (value "0R22")
      (footprint "RESC3216X65N")
      (description "Resistor - 1%")
      (fields
        (field (name "PART NUMBER") "R1206_0R22_1%_0.5W_600PPM")
        (field (name "POWER") "0.5W")
        (field (name "AUTHOR") "CERN DEM JMW")
      )
      (libsource (lib "Resistors") (part "Resistor - 1%"))
    )
    (comp (ref "R193")
      (value "0R22")
      (footprint "RESC3216X65N")
      (description "Resistor - 1%")
      (fields
        (field (name "PART NUMBER") "R1206_0R22_1%_0.5W_600PPM")
        (field (name "POWER") "0.5W")
        (field (name "AUTHOR") "CERN DEM JMW")
      )
      (libsource (lib "Resistors") (part "Resistor - 1%"))
    )
    (comp (ref "R194")
      (value "39")
      (footprint "RESC1608X55N")
      (description "Resistor - 1%")
      (fields
        (field (name "PART NUMBER") "R0603_39R_1%_0.1W_100PPM")
        (field (name "POWER") "0.1W")
        (field (name "AUTHOR") "CERN DEM JLC")
      )
      (libsource (lib "Resistors") (part "Resistor - 1%"))
    )
    (comp (ref "T3")
      (value "IRF9910Pbf")
      (footprint "SOIC127P600X175-8N")
      (description "Dual SO-8 MOSFET For POL Cconverter")
      (fields (field (name "MANUFACTURER") "INTERNATIONAL RECTIFIER") (field (name "AUTHOR") "CERN DEM JLC"))
      (libsource (lib "ICs And Semiconductors") (part "IRF9910"))
    )
    (comp (ref "T4")
      (value "IRF9910Pbf")
      (footprint "SOIC127P600X175-8N")
      (description "Dual SO-8 MOSFET For POL Cconverter")
      (fields (field (name "MANUFACTURER") "INTERNATIONAL RECTIFIER") (field (name "AUTHOR") "CERN DEM JLC"))
      (libsource (lib "ICs And Semiconductors") (part "IRF9910"))
    )
    (comp (ref "T7")
      (value "IRF9910Pbf")
      (footprint "SOIC127P600X175-8N")
      (description "Dual SO-8 MOSFET For POL Cconverter")
      (fields (field (name "MANUFACTURER") "INTERNATIONAL RECTIFIER") (field (name "AUTHOR") "CERN DEM JLC"))
      (libsource (lib "ICs And Semiconductors") (part "IRF9910"))
    )
    (comp (ref "T9")
      (value "IRF9910Pbf")
      (footprint "SOIC127P600X175-8N")
      (description "Dual SO-8 MOSFET For POL Cconverter")
      (fields (field (name "MANUFACTURER") "INTERNATIONAL RECTIFIER") (field (name "AUTHOR") "CERN DEM JLC"))
      (libsource (lib "ICs And Semiconductors") (part "IRF9910"))
    )
    (comp (ref "T11")
      (value "BSH103")
      (footprint "SOT95P230X110-3N")
      (description "N-CHANNEL MOSFET WITH DIODE")
      (fields (field (name "MANUFACTURER") "NXP SEMICONDUCTORS") (field (name "AUTHOR") "CERN DEM JLC"))
      (libsource (lib "ICs And Semiconductors") (part "N-MOSFET-D 1G 2S 3D"))
    )
    (comp (ref "T12")
      (value "IRF9910Pbf")
      (footprint "SOIC127P600X175-8N")
      (description "Dual SO-8 MOSFET For POL Cconverter")
      (fields (field (name "MANUFACTURER") "INTERNATIONAL RECTIFIER") (field (name "AUTHOR") "CERN DEM JLC"))
      (libsource (lib "ICs And Semiconductors") (part "IRF9910"))
    )
  )
  (nets
    (net (code "1") (name "/EN_DC_DC") (class "Default")
      (node (ref "IC18") (pin "3") (pinfunction "DIS/~{EN}_3") (pintype "input"))
      (node (ref "IC2") (pin "24") (pinfunction "EN1_24") (pintype "input"))
      (node (ref "IC2") (pin "7") (pinfunction "EN2_7") (pintype "input"))
      (node (ref "IC9") (pin "24") (pinfunction "EN1_24") (pintype "input"))
      (node (ref "IC9") (pin "7") (pinfunction "EN2_7") (pintype "input"))
      (node (ref "R60") (pin "1") (pinfunction "1_1") (pintype "passive"))
    )
    (net (code "2") (name "/Isense") (class "Default")
      (node (ref "R186") (pin "1") (pinfunction "1_1") (pintype "passive"))
      (node (ref "R189") (pin "2") (pinfunction "2_2") (pintype "passive"))
      (node (ref "R193") (pin "2") (pinfunction "2_2") (pintype "passive"))
      (node (ref "T12") (pin "1") (pinfunction "S_1") (pintype "passive"))
      (node (ref "T12") (pin "3") (pinfunction "S_3") (pintype "passive"))
    )
    (net (code "3") (name "/RSTn") (class "Default")
      (node (ref "IC23") (pin "2") (pinfunction "~{RST}_2") (pintype "output"))
    )
    (net (code "4") (name "/SW") (class "Default")
      (node (ref "D1") (pin "1") (pinfunction "A_1") (pintype "passive"))
      (node (ref "D1") (pin "2") (pinfunction "A_2") (pintype "passive"))
      (node (ref "L14") (pin "2") (pinfunction "2_2") (pintype "passive"))
      (node (ref "T12") (pin "5") (pinfunction "D_5") (pintype "passive"))
      (node (ref "T12") (pin "6") (pinfunction "D_6") (pintype "passive"))
      (node (ref "T12") (pin "7") (pinfunction "D_7") (pintype "passive"))
      (node (ref "T12") (pin "8") (pinfunction "D_8") (pintype "passive"))
    )
    (net (code "5") (name "GND") (class "Default")
      (node (ref "B10") (pin "1") (pinfunction "1_1") (pintype "bidirectional"))
      (node (ref "C101") (pin "1") (pinfunction "1_1") (pintype "passive"))
      (node (ref "C102") (pin "1") (pinfunction "1_1") (pintype "passive"))
      (node (ref "C117") (pin "1") (pinfunction "1_1") (pintype "passive"))
      (node (ref "C118") (pin "1") (pinfunction "1_1") (pintype "passive"))
      (node (ref "C119") (pin "1") (pinfunction "1_1") (pintype "passive"))
      (node (ref "C128") (pin "1") (pinfunction "1_1") (pintype "passive"))
      (node (ref "C135") (pin "1") (pinfunction "1_1") (pintype "passive"))
      (node (ref "C136") (pin "1") (pinfunction "1_1") (pintype "passive"))
      (node (ref "C137") (pin "1") (pinfunction "1_1") (pintype "passive"))
      (node (ref "C138") (pin "1") (pinfunction "1_1") (pintype "passive"))
      (node (ref "C139") (pin "1") (pinfunction "1_1") (pintype "passive"))
      (node (ref "C148") (pin "1") (pinfunction "1_1") (pintype "passive"))
      (node (ref "C163") (pin "1") (pinfunction "1_1") (pintype "passive"))
      (node (ref "C169") (pin "1") (pinfunction "1_1") (pintype "passive"))
      (node (ref "C173") (pin "1") (pinfunction "1_1") (pintype "passive"))
      (node (ref "C175") (pin "2") (pinfunction "2_2") (pintype "passive"))
      (node (ref "C176") (pin "2") (pinfunction "2_2") (pintype "passive"))
      (node (ref "C179") (pin "2") (pinfunction "2_2") (pintype "passive"))
      (node (ref "C180") (pin "1") (pinfunction "1_1") (pintype "passive"))
      (node (ref "C181") (pin "1") (pinfunction "1_1") (pintype "passive"))
      (node (ref "C182") (pin "2") (pinfunction "2_2") (pintype "passive"))
      (node (ref "C183") (pin "1") (pinfunction "1_1") (pintype "passive"))
      (node (ref "C209") (pin "1") (pinfunction "1_1") (pintype "passive"))
      (node (ref "C210") (pin "1") (pinfunction "1_1") (pintype "passive"))
      (node (ref "C211") (pin "2") (pinfunction "2_2") (pintype "passive"))
      (node (ref "C212") (pin "1") (pinfunction "1_1") (pintype "passive"))
      (node (ref "C218") (pin "1") (pinfunction "1_1") (pintype "passive"))
      (node (ref "C224") (pin "2") (pinfunction "2_2") (pintype "passive"))
      (node (ref "C225") (pin "2") (pinfunction "2_2") (pintype "passive"))
      (node (ref "C241") (pin "2") (pinfunction "2_2") (pintype "passive"))
      (node (ref "C298") (pin "1") (pinfunction "1_1") (pintype "passive"))
      (node (ref "C299") (pin "1") (pinfunction "1_1") (pintype "passive"))
      (node (ref "C300") (pin "1") (pinfunction "1_1") (pintype "passive"))
      (node (ref "C309") (pin "1") (pinfunction "1_1") (pintype "passive"))
      (node (ref "C31") (pin "1") (pinfunction "1_1") (pintype "passive"))
      (node (ref "C310") (pin "1") (pinfunction "1_1") (pintype "passive"))
      (node (ref "C316") (pin "1") (pinfunction "1_1") (pintype "passive"))
      (node (ref "C321") (pin "1") (pinfunction "1_1") (pintype "passive"))
      (node (ref "C322") (pin "1") (pinfunction "1_1") (pintype "passive"))
      (node (ref "C33") (pin "1") (pinfunction "1_1") (pintype "passive"))
      (node (ref "C35") (pin "1") (pinfunction "1_1") (pintype "passive"))
      (node (ref "C412") (pin "2") (pinfunction "2_2") (pintype "passive"))
      (node (ref "C43") (pin "1") (pinfunction "1_1") (pintype "passive"))
      (node (ref "C435") (pin "2") (pinfunction "2_2") (pintype "passive"))
      (node (ref "C44") (pin "2") (pinfunction "2_2") (pintype "passive"))
      (node (ref "C45") (pin "1") (pinfunction "1_1") (pintype "passive"))
      (node (ref "C46") (pin "1") (pinfunction "1_1") (pintype "passive"))
      (node (ref "C47") (pin "1") (pinfunction "1_1") (pintype "passive"))
      (node (ref "C49") (pin "1") (pinfunction "1_1") (pintype "passive"))
      (node (ref "C5") (pin "1") (pinfunction "1_1") (pintype "passive"))
      (node (ref "C60") (pin "2") (pinfunction "2_2") (pintype "passive"))
      (node (ref "C61") (pin "1") (pinfunction "1_1") (pintype "passive"))
      (node (ref "C62") (pin "1") (pinfunction "1_1") (pintype "passive"))
      (node (ref "C66") (pin "1") (pinfunction "1_1") (pintype "passive"))
      (node (ref "C67") (pin "1") (pinfunction "1_1") (pintype "passive"))
      (node (ref "C68") (pin "1") (pinfunction "1_1") (pintype "passive"))
      (node (ref "C71") (pin "1") (pinfunction "1_1") (pintype "passive"))
      (node (ref "C72") (pin "1") (pinfunction "1_1") (pintype "passive"))
      (node (ref "C77") (pin "1") (pinfunction "1_1") (pintype "passive"))
      (node (ref "C90") (pin "1") (pinfunction "1_1") (pintype "passive"))
      (node (ref "C91") (pin "1") (pinfunction "1_1") (pintype "passive"))
      (node (ref "C93") (pin "1") (pinfunction "1_1") (pintype "passive"))
      (node (ref "IC18") (pin "11") (pinfunction "PAD_11") (pintype "power_in"))
      (node (ref "IC18") (pin "6") (pinfunction "GND_6") (pintype "power_in"))
      (node (ref "IC2") (pin "12") (pinfunction "PGND2_12") (pintype "power_in"))
      (node (ref "IC2") (pin "14") (pinfunction "TEST2_14") (pintype "input"))
      (node (ref "IC2") (pin "19") (pinfunction "PGND1_19") (pintype "power_in"))
      (node (ref "IC2") (pin "25") (pinfunction "EP_25") (pintype "power_in"))
      (node (ref "IC2") (pin "3") (pinfunction "GND_3") (pintype "power_in"))
      (node (ref "IC2") (pin "4") (pinfunction "TEST1_4") (pintype "output"))
      (node (ref "IC23") (pin "1") (pinfunction "VSS_1") (pintype "power_in"))
      (node (ref "IC8") (pin "11") (pinfunction "EP_11") (pintype "power_in"))
      (node (ref "IC8") (pin "4") (pinfunction "PGND_4") (pintype "power_in"))
      (node (ref "IC8") (pin "8") (pinfunction "GND_8") (pintype "power_in"))
      (node (ref "IC9") (pin "12") (pinfunction "PGND2_12") (pintype "power_in"))
      (node (ref "IC9") (pin "14") (pinfunction "TEST2_14") (pintype "input"))
      (node (ref "IC9") (pin "19") (pinfunction "PGND1_19") (pintype "power_in"))
      (node (ref "IC9") (pin "25") (pinfunction "EP_25") (pintype "power_in"))
      (node (ref "IC9") (pin "3") (pinfunction "GND_3") (pintype "power_in"))
      (node (ref "IC9") (pin "4") (pinfunction "TEST1_4") (pintype "output"))
      (node (ref "J1") (pin "13") (pinfunction "13_13") (pintype "bidirectional"))
      (node (ref "J1") (pin "15") (pinfunction "15_15") (pintype "bidirectional"))
      (node (ref "J1") (pin "16") (pinfunction "16_16") (pintype "bidirectional"))
      (node (ref "J1") (pin "17") (pinfunction "17_17") (pintype "bidirectional"))
      (node (ref "J1") (pin "3") (pinfunction "3_3") (pintype "bidirectional"))
      (node (ref "J1") (pin "5") (pinfunction "5_5") (pintype "bidirectional"))
      (node (ref "J1") (pin "7") (pinfunction "7_7") (pintype "bidirectional"))
      (node (ref "LD15") (pin "1") (pinfunction "C_1") (pintype "passive"))
      (node (ref "R11") (pin "1") (pinfunction "1_1") (pintype "passive"))
      (node (ref "R12") (pin "1") (pinfunction "1_1") (pintype "passive"))
      (node (ref "R120") (pin "1") (pinfunction "1_1") (pintype "passive"))
      (node (ref "R128") (pin "1") (pinfunction "1_1") (pintype "passive"))
      (node (ref "R146") (pin "2") (pinfunction "2_2") (pintype "passive"))
      (node (ref "R153") (pin "2") (pinfunction "2_2") (pintype "passive"))
      (node (ref "R154") (pin "1") (pinfunction "1_1") (pintype "passive"))
      (node (ref "R155") (pin "1") (pinfunction "1_1") (pintype "passive"))
      (node (ref "R156") (pin "2") (pinfunction "2_2") (pintype "passive"))
      (node (ref "R170") (pin "1") (pinfunction "1_1") (pintype "passive"))
      (node (ref "R171") (pin "1") (pinfunction "1_1") (pintype "passive"))
      (node (ref "R189") (pin "1") (pinfunction "1_1") (pintype "passive"))
      (node (ref "R193") (pin "1") (pinfunction "1_1") (pintype "passive"))
      (node (ref "R22") (pin "1") (pinfunction "1_1") (pintype "passive"))
      (node (ref "T11") (pin "2") (pinfunction "S_2") (pintype "passive"))
      (node (ref "T3") (pin "1") (pinfunction "S_1") (pintype "passive"))
      (node (ref "T4") (pin "1") (pinfunction "S_1") (pintype "passive"))
      (node (ref "T7") (pin "1") (pinfunction "S_1") (pintype "passive"))
      (node (ref "T9") (pin "1") (pinfunction "S_1") (pintype "passive"))
    )
    (net (code "6") (name "Net-(C78-Pad2)") (class "Default")
      (node (ref "C78") (pin "2") (pinfunction "2_2") (pintype "passive"))
      (node (ref "R130") (pin "1") (pinfunction "1_1") (pintype "passive"))
    )
    (net (code "7") (name "Net-(IC2-DRVH1)") (class "Default")
      (node (ref "IC2") (pin "22") (pinfunction "DRVH1_22") (pintype "output"))
      (node (ref "T7") (pin "4") (pinfunction "G_4") (pintype "passive"))
    )
    (net (code "8") (name "Net-(IC2-DRVH2)") (class "Default")
      (node (ref "IC2") (pin "9") (pinfunction "DRVH2_9") (pintype "output"))
      (node (ref "T9") (pin "4") (pinfunction "G_4") (pintype "passive"))
    )
    (net (code "9") (name "Net-(IC2-DRVL1)") (class "Default")
      (node (ref "IC2") (pin "20") (pinfunction "DRVL1_20") (pintype "output"))
      (node (ref "T7") (pin "2") (pinfunction "G_2") (pintype "passive"))
    )
    (net (code "10") (name "Net-(IC2-DRVL2)") (class "Default")
      (node (ref "IC2") (pin "11") (pinfunction "DRVL2_11") (pintype "output"))
      (node (ref "T9") (pin "2") (pinfunction "G_2") (pintype "passive"))
    )
    (net (code "11") (name "Net-(IC2-SW1)") (class "Default")
      (node (ref "C167") (pin "2") (pinfunction "2_2") (pintype "passive"))
      (node (ref "IC2") (pin "21") (pinfunction "SW1_21") (pintype "bidirectional"))
      (node (ref "L12") (pin "1") (pinfunction "1_1") (pintype "passive"))
      (node (ref "T7") (pin "3") (pinfunction "S_3") (pintype "passive"))
      (node (ref "T7") (pin "7") (pinfunction "D_7") (pintype "passive"))
      (node (ref "T7") (pin "8") (pinfunction "D_8") (pintype "passive"))
    )
    (net (code "12") (name "Net-(IC2-SW2)") (class "Default")
      (node (ref "C195") (pin "2") (pinfunction "2_2") (pintype "passive"))
      (node (ref "IC2") (pin "10") (pinfunction "SW2_10") (pintype "bidirectional"))
      (node (ref "L13") (pin "1") (pinfunction "1_1") (pintype "passive"))
      (node (ref "T9") (pin "3") (pinfunction "S_3") (pintype "passive"))
      (node (ref "T9") (pin "7") (pinfunction "D_7") (pintype "passive"))
      (node (ref "T9") (pin "8") (pinfunction "D_8") (pintype "passive"))
    )
    (net (code "13") (name "Net-(IC2-TRIP1)") (class "Default")
      (node (ref "IC2") (pin "18") (pinfunction "TRIP1_18") (pintype "input"))
      (node (ref "R12") (pin "2") (pinfunction "2_2") (pintype "passive"))
    )
    (net (code "14") (name "Net-(IC2-TRIP2)") (class "Default")
      (node (ref "IC2") (pin "13") (pinfunction "TRIP2_13") (pintype "input"))
      (node (ref "R155") (pin "2") (pinfunction "2_2") (pintype "passive"))
    )
    (net (code "15") (name "Net-(IC2-V5FILT)") (class "Default")
      (node (ref "C300") (pin "2") (pinfunction "2_2") (pintype "passive"))
      (node (ref "IC2") (pin "15") (pinfunction "V5FILT_15") (pintype "input"))
    )
    (net (code "16") (name "Net-(IC2-VBST1)") (class "Default")
      (node (ref "C167") (pin "1") (pinfunction "1_1") (pintype "passive"))
      (node (ref "IC2") (pin "23") (pinfunction "VBST1_23") (pintype "input"))
    )
    (net (code "17") (name "Net-(IC2-VBST2)") (class "Default")
      (node (ref "C195") (pin "1") (pinfunction "1_1") (pintype "passive"))
      (node (ref "IC2") (pin "8") (pinfunction "VBST2_8") (pintype "input"))
    )
    (net (code "18") (name "Net-(IC2-VFB1)") (class "Default")
      (node (ref "IC2") (pin "2") (pinfunction "VFB1_2") (pintype "input"))
      (node (ref "R128") (pin "2") (pinfunction "2_2") (pintype "passive"))
      (node (ref "R168") (pin "1") (pinfunction "1_1") (pintype "passive"))
    )
    (net (code "19") (name "Net-(IC2-VFB2)") (class "Default")
      (node (ref "IC2") (pin "5") (pinfunction "VFB2_5") (pintype "input"))
      (node (ref "R129") (pin "1") (pinfunction "1_1") (pintype "passive"))
      (node (ref "R156") (pin "1") (pinfunction "1_1") (pintype "passive"))
      (node (ref "R26") (pin "2") (pinfunction "2_2") (pintype "passive"))
    )
    (net (code "20") (name "Net-(IC2-VREG5)") (class "Default")
      (node (ref "C35") (pin "2") (pinfunction "2_2") (pintype "passive"))
      (node (ref "IC2") (pin "16") (pinfunction "VREG5_16") (pintype "output"))
    )
    (net (code "21") (name "Net-(IC8-PGOOD)") (class "Default")
      (node (ref "IC8") (pin "9") (pinfunction "PGOOD_9") (pintype "output"))
      (node (ref "R150") (pin "1") (pinfunction "1_1") (pintype "passive"))
      (node (ref "T11") (pin "1") (pinfunction "G_1") (pintype "passive"))
    )
    (net (code "22") (name "Net-(IC8-REFIN)") (class "Default")
      (node (ref "C43") (pin "2") (pinfunction "2_2") (pintype "passive"))
      (node (ref "IC8") (pin "1") (pinfunction "REFIN_1") (pintype "input"))
      (node (ref "R146") (pin "1") (pinfunction "1_1") (pintype "passive"))
      (node (ref "R187") (pin "1") (pinfunction "1_1") (pintype "passive"))
    )
    (net (code "23") (name "Net-(IC9-DRVH1)") (class "Default")
      (node (ref "IC9") (pin "22") (pinfunction "DRVH1_22") (pintype "output"))
      (node (ref "T3") (pin "4") (pinfunction "G_4") (pintype "passive"))
    )
    (net (code "24") (name "Net-(IC9-DRVH2)") (class "Default")
      (node (ref "IC9") (pin "9") (pinfunction "DRVH2_9") (pintype "output"))
      (node (ref "T4") (pin "4") (pinfunction "G_4") (pintype "passive"))
    )
    (net (code "25") (name "Net-(IC9-DRVL1)") (class "Default")
      (node (ref "IC9") (pin "20") (pinfunction "DRVL1_20") (pintype "output"))
      (node (ref "T3") (pin "2") (pinfunction "G_2") (pintype "passive"))
    )
    (net (code "26") (name "Net-(IC9-DRVL2)") (class "Default")
      (node (ref "IC9") (pin "11") (pinfunction "DRVL2_11") (pintype "output"))
      (node (ref "T4") (pin "2") (pinfunction "G_2") (pintype "passive"))
    )
    (net (code "27") (name "Net-(IC9-SW1)") (class "Default")
      (node (ref "C38") (pin "2") (pinfunction "2_2") (pintype "passive"))
      (node (ref "IC9") (pin "21") (pinfunction "SW1_21") (pintype "bidirectional"))
      (node (ref "L3") (pin "1") (pinfunction "1_1") (pintype "passive"))
      (node (ref "T3") (pin "3") (pinfunction "S_3") (pintype "passive"))
      (node (ref "T3") (pin "7") (pinfunction "D_7") (pintype "passive"))
      (node (ref "T3") (pin "8") (pinfunction "D_8") (pintype "passive"))
    )
    (net (code "28") (name "Net-(IC9-SW2)") (class "Default")
      (node (ref "C39") (pin "2") (pinfunction "2_2") (pintype "passive"))
      (node (ref "IC9") (pin "10") (pinfunction "SW2_10") (pintype "bidirectional"))
      (node (ref "L4") (pin "1") (pinfunction "1_1") (pintype "passive"))
      (node (ref "T4") (pin "3") (pinfunction "S_3") (pintype "passive"))
      (node (ref "T4") (pin "7") (pinfunction "D_7") (pintype "passive"))
      (node (ref "T4") (pin "8") (pinfunction "D_8") (pintype "passive"))
    )
    (net (code "29") (name "Net-(IC9-TRIP1)") (class "Default")
      (node (ref "IC9") (pin "18") (pinfunction "TRIP1_18") (pintype "input"))
      (node (ref "R120") (pin "2") (pinfunction "2_2") (pintype "passive"))
    )
    (net (code "30") (name "Net-(IC9-TRIP2)") (class "Default")
      (node (ref "IC9") (pin "13") (pinfunction "TRIP2_13") (pintype "input"))
      (node (ref "R11") (pin "2") (pinfunction "2_2") (pintype "passive"))
    )
    (net (code "31") (name "Net-(IC9-V5FILT)") (class "Default")
      (node (ref "C5") (pin "2") (pinfunction "2_2") (pintype "passive"))
      (node (ref "IC9") (pin "15") (pinfunction "V5FILT_15") (pintype "input"))
    )
    (net (code "32") (name "Net-(IC9-VBST1)") (class "Default")
      (node (ref "C38") (pin "1") (pinfunction "1_1") (pintype "passive"))
      (node (ref "IC9") (pin "23") (pinfunction "VBST1_23") (pintype "input"))
    )
    (net (code "33") (name "Net-(IC9-VBST2)") (class "Default")
      (node (ref "C39") (pin "1") (pinfunction "1_1") (pintype "passive"))
      (node (ref "IC9") (pin "8") (pinfunction "VBST2_8") (pintype "input"))
    )
    (net (code "34") (name "Net-(IC9-VFB1)") (class "Default")
      (node (ref "IC9") (pin "2") (pinfunction "VFB1_2") (pintype "input"))
      (node (ref "R147") (pin "1") (pinfunction "1_1") (pintype "passive"))
      (node (ref "R22") (pin "2") (pinfunction "2_2") (pintype "passive"))
    )
    (net (code "35") (name "Net-(IC9-VFB2)") (class "Default")
      (node (ref "IC9") (pin "5") (pinfunction "VFB2_5") (pintype "input"))
      (node (ref "R125") (pin "2") (pinfunction "2_2") (pintype "passive"))
      (node (ref "R153") (pin "1") (pinfunction "1_1") (pintype "passive"))
    )
    (net (code "36") (name "Net-(IC9-VREG5)") (class "Default")
      (node (ref "C173") (pin "2") (pinfunction "2_2") (pintype "passive"))
      (node (ref "IC9") (pin "16") (pinfunction "VREG5_16") (pintype "output"))
    )
    (net (code "37") (name "Net-(IC18-BP)") (class "Default")
      (node (ref "C33") (pin "2") (pinfunction "2_2") (pintype "passive"))
      (node (ref "IC18") (pin "9") (pinfunction "BP_9") (pintype "passive"))
    )
    (net (code "38") (name "Net-(IC18-COMP)") (class "Default")
      (node (ref "C100") (pin "2") (pinfunction "2_2") (pintype "passive"))
      (node (ref "C116") (pin "2") (pinfunction "2_2") (pintype "passive"))
      (node (ref "C79") (pin "2") (pinfunction "2_2") (pintype "passive"))
      (node (ref "IC18") (pin "4") (pinfunction "COMP_4") (pintype "output"))
      (node (ref "R169") (pin "2") (pinfunction "2_2") (pintype "passive"))
    )
    (net (code "39") (name "Net-(IC18-FB)") (class "Default")
      (node (ref "C100") (pin "1") (pinfunction "1_1") (pintype "passive"))
      (node (ref "C116") (pin "1") (pinfunction "1_1") (pintype "passive"))
      (node (ref "C78") (pin "1") (pinfunction "1_1") (pintype "passive"))
      (node (ref "C79") (pin "1") (pinfunction "1_1") (pintype "passive"))
      (node (ref "IC18") (pin "5") (pinfunction "FB_5") (pintype "input"))
      (node (ref "R170") (pin "2") (pinfunction "2_2") (pintype "passive"))
      (node (ref "R171") (pin "2") (pinfunction "2_2") (pintype "passive"))
      (node (ref "R183") (pin "1") (pinfunction "1_1") (pintype "passive"))
    )
    (net (code "40") (name "Net-(IC18-GDRV)") (class "Default")
      (node (ref "IC18") (pin "8") (pinfunction "GDRV_8") (pintype "output"))
      (node (ref "R184") (pin "2") (pinfunction "2_2") (pintype "passive"))
      (node (ref "R194") (pin "1") (pinfunction "1_1") (pintype "passive"))
    )
    (net (code "41") (name "Net-(IC18-ISNS)") (class "Default")
      (node (ref "C298") (pin "2") (pinfunction "2_2") (pintype "passive"))
      (node (ref "C299") (pin "2") (pinfunction "2_2") (pintype "passive"))
      (node (ref "IC18") (pin "7") (pinfunction "ISNS_7") (pintype "input"))
      (node (ref "R186") (pin "2") (pinfunction "2_2") (pintype "passive"))
    )
    (net (code "42") (name "Net-(IC18-RC)") (class "Default")
      (node (ref "C101") (pin "2") (pinfunction "2_2") (pintype "passive"))
      (node (ref "IC18") (pin "1") (pinfunction "RC_1") (pintype "passive"))
      (node (ref "R178") (pin "1") (pinfunction "1_1") (pintype "passive"))
    )
    (net (code "43") (name "Net-(IC18-SS)") (class "Default")
      (node (ref "C102") (pin "2") (pinfunction "2_2") (pintype "passive"))
      (node (ref "IC18") (pin "2") (pinfunction "SS_2") (pintype "passive"))
    )
    (net (code "44") (name "Net-(J1-Pad8)") (class "Default")
      (node (ref "J1") (pin "8") (pinfunction "8_8") (pintype "bidirectional"))
      (node (ref "R121") (pin "1") (pinfunction "1_1") (pintype "passive"))
    )
    (net (code "45") (name "Net-(J1-Pad14)") (class "Default")
      (node (ref "J1") (pin "14") (pinfunction "14_14") (pintype "bidirectional"))
      (node (ref "R154") (pin "2") (pinfunction "2_2") (pintype "passive"))
    )
    (net (code "46") (name "Net-(LD15-A)") (class "Default")
      (node (ref "LD15") (pin "2") (pinfunction "A_2") (pintype "passive"))
      (node (ref "R112") (pin "1") (pinfunction "1_1") (pintype "passive"))
    )
    (net (code "47") (name "Net-(LD19-A)") (class "Default")
      (node (ref "LD19") (pin "2") (pinfunction "A_2") (pintype "passive"))
      (node (ref "R134") (pin "1") (pinfunction "1_1") (pintype "passive"))
    )
    (net (code "48") (name "Net-(LD19-C)") (class "Default")
      (node (ref "LD19") (pin "1") (pinfunction "C_1") (pintype "passive"))
      (node (ref "T11") (pin "3") (pinfunction "D_3") (pintype "passive"))
    )
    (net (code "49") (name "Net-(R130-Pad2)") (class "Default")
      (node (ref "R130") (pin "2") (pinfunction "2_2") (pintype "passive"))
      (node (ref "R167") (pin "2") (pinfunction "2_2") (pintype "passive"))
    )
    (net (code "50") (name "Net-(R167-Pad1)") (class "Default")
      (node (ref "R167") (pin "1") (pinfunction "1_1") (pintype "passive"))
      (node (ref "R169") (pin "1") (pinfunction "1_1") (pintype "passive"))
    )
    (net (code "51") (name "Net-(T12A-G)") (class "Default")
      (node (ref "R184") (pin "1") (pinfunction "1_1") (pintype "passive"))
      (node (ref "T12") (pin "4") (pinfunction "G_4") (pintype "passive"))
    )
    (net (code "52") (name "Net-(T12B-G)") (class "Default")
      (node (ref "R194") (pin "2") (pinfunction "2_2") (pintype "passive"))
      (node (ref "T12") (pin "2") (pinfunction "G_2") (pintype "passive"))
    )
    (net (code "53") (name "P1V2") (class "Default")
      (node (ref "B6") (pin "1") (pinfunction "1_1") (pintype "bidirectional"))
      (node (ref "C169") (pin "2") (pinfunction "2_2") (pintype "passive"))
      (node (ref "C181") (pin "2") (pinfunction "2_2") (pintype "passive"))
      (node (ref "C183") (pin "2") (pinfunction "2_2") (pintype "passive"))
      (node (ref "C209") (pin "2") (pinfunction "2_2") (pintype "passive"))
      (node (ref "C210") (pin "2") (pinfunction "2_2") (pintype "passive"))
      (node (ref "C212") (pin "2") (pinfunction "2_2") (pintype "passive"))
      (node (ref "C224") (pin "1") (pinfunction "1_1") (pintype "passive"))
      (node (ref "C225") (pin "1") (pinfunction "1_1") (pintype "passive"))
      (node (ref "C45") (pin "2") (pinfunction "2_2") (pintype "passive"))
      (node (ref "C46") (pin "2") (pinfunction "2_2") (pintype "passive"))
      (node (ref "C47") (pin "2") (pinfunction "2_2") (pintype "passive"))
      (node (ref "C49") (pin "2") (pinfunction "2_2") (pintype "passive"))
      (node (ref "IC2") (pin "6") (pinfunction "VO2_6") (pintype "input"))
      (node (ref "L13") (pin "2") (pinfunction "2_2") (pintype "passive"))
      (node (ref "R129") (pin "2") (pinfunction "2_2") (pintype "passive"))
      (node (ref "R26") (pin "1") (pinfunction "1_1") (pintype "passive"))
    )
    (net (code "54") (name "P1V5") (class "Default")
      (node (ref "C163") (pin "2") (pinfunction "2_2") (pintype "passive"))
      (node (ref "C182") (pin "1") (pinfunction "1_1") (pintype "passive"))
      (node (ref "C66") (pin "2") (pinfunction "2_2") (pintype "passive"))
      (node (ref "C90") (pin "2") (pinfunction "2_2") (pintype "passive"))
      (node (ref "C93") (pin "2") (pinfunction "2_2") (pintype "passive"))
      (node (ref "IC2") (pin "1") (pinfunction "VO1_1") (pintype "input"))
      (node (ref "IC8") (pin "2") (pinfunction "VLDOIN_2") (pintype "input"))
      (node (ref "L12") (pin "2") (pinfunction "2_2") (pintype "passive"))
      (node (ref "R168") (pin "2") (pinfunction "2_2") (pintype "passive"))
      (node (ref "R187") (pin "2") (pinfunction "2_2") (pintype "passive"))
    )
    (net (code "55") (name "P1V8") (class "Default")
      (node (ref "B2") (pin "1") (pinfunction "1_1") (pintype "bidirectional"))
    )
    (net (code "56") (name "P2V5") (class "Default")
      (node (ref "B9") (pin "1") (pinfunction "1_1") (pintype "bidirectional"))
      (node (ref "C128") (pin "2") (pinfunction "2_2") (pintype "passive"))
      (node (ref "C139") (pin "2") (pinfunction "2_2") (pintype "passive"))
      (node (ref "C148") (pin "2") (pinfunction "2_2") (pintype "passive"))
      (node (ref "C60") (pin "1") (pinfunction "1_1") (pintype "passive"))
      (node (ref "C72") (pin "2") (pinfunction "2_2") (pintype "passive"))
      (node (ref "C77") (pin "2") (pinfunction "2_2") (pintype "passive"))
      (node (ref "IC9") (pin "6") (pinfunction "VO2_6") (pintype "input"))
      (node (ref "L4") (pin "2") (pinfunction "2_2") (pintype "passive"))
      (node (ref "R125") (pin "1") (pinfunction "1_1") (pintype "passive"))
    )
    (net (code "57") (name "P2V5_FMC1") (class "Default")
      (node (ref "C119") (pin "2") (pinfunction "2_2") (pintype "passive"))
      (node (ref "C135") (pin "2") (pinfunction "2_2") (pintype "passive"))
      (node (ref "C136") (pin "2") (pinfunction "2_2") (pintype "passive"))
      (node (ref "C137") (pin "2") (pinfunction "2_2") (pintype "passive"))
      (node (ref "C138") (pin "2") (pinfunction "2_2") (pintype "passive"))
      (node (ref "C176") (pin "1") (pinfunction "1_1") (pintype "passive"))
      (node (ref "C179") (pin "1") (pinfunction "1_1") (pintype "passive"))
      (node (ref "IC9") (pin "1") (pinfunction "VO1_1") (pintype "input"))
      (node (ref "L3") (pin "2") (pinfunction "2_2") (pintype "passive"))
      (node (ref "R147") (pin "2") (pinfunction "2_2") (pintype "passive"))
    )
    (net (code "58") (name "P3V3") (class "Default")
      (node (ref "B8") (pin "1") (pinfunction "1_1") (pintype "bidirectional"))
      (node (ref "C61") (pin "2") (pinfunction "2_2") (pintype "passive"))
      (node (ref "F3") (pin "1") (pinfunction "1_1") (pintype "passive"))
      (node (ref "F4") (pin "1") (pinfunction "1_1") (pintype "passive"))
      (node (ref "IC23") (pin "3") (pinfunction "VDD_3") (pintype "power_in"))
      (node (ref "IC8") (pin "10") (pinfunction "VIN_10") (pintype "power_in"))
      (node (ref "IC8") (pin "7") (pinfunction "EN_7") (pintype "input"))
      (node (ref "J1") (pin "1") (pinfunction "1_1") (pintype "bidirectional"))
      (node (ref "J1") (pin "11") (pinfunction "11_11") (pintype "bidirectional"))
      (node (ref "J1") (pin "2") (pinfunction "2_2") (pintype "bidirectional"))
      (node (ref "R112") (pin "2") (pinfunction "2_2") (pintype "passive"))
      (node (ref "R134") (pin "2") (pinfunction "2_2") (pintype "passive"))
      (node (ref "R150") (pin "2") (pinfunction "2_2") (pintype "passive"))
    )
    (net (code "59") (name "P3V3_FMC1") (class "Default")
      (node (ref "F3") (pin "2") (pinfunction "2_2") (pintype "passive"))
    )
    (net (code "60") (name "P3V3_FMC2") (class "Default")
      (node (ref "F4") (pin "2") (pinfunction "2_2") (pintype "passive"))
    )
    (net (code "61") (name "P5V_VME") (class "Default")
      (node (ref "B1") (pin "1") (pinfunction "1_1") (pintype "bidirectional"))
      (node (ref "C117") (pin "2") (pinfunction "2_2") (pintype "passive"))
      (node (ref "C118") (pin "2") (pinfunction "2_2") (pintype "passive"))
      (node (ref "C211") (pin "1") (pinfunction "1_1") (pintype "passive"))
      (node (ref "C218") (pin "2") (pinfunction "2_2") (pintype "passive"))
      (node (ref "C309") (pin "2") (pinfunction "2_2") (pintype "passive"))
      (node (ref "C31") (pin "2") (pinfunction "2_2") (pintype "passive"))
      (node (ref "C310") (pin "2") (pinfunction "2_2") (pintype "passive"))
      (node (ref "C316") (pin "2") (pinfunction "2_2") (pintype "passive"))
      (node (ref "C321") (pin "2") (pinfunction "2_2") (pintype "passive"))
      (node (ref "C322") (pin "2") (pinfunction "2_2") (pintype "passive"))
      (node (ref "C44") (pin "1") (pinfunction "1_1") (pintype "passive"))
      (node (ref "C67") (pin "2") (pinfunction "2_2") (pintype "passive"))
      (node (ref "C71") (pin "2") (pinfunction "2_2") (pintype "passive"))
      (node (ref "C91") (pin "2") (pinfunction "2_2") (pintype "passive"))
      (node (ref "IC18") (pin "10") (pinfunction "Vdd_10") (pintype "power_in"))
      (node (ref "IC2") (pin "17") (pinfunction "VIN_17") (pintype "input"))
      (node (ref "IC9") (pin "17") (pinfunction "VIN_17") (pintype "input"))
      (node (ref "J1") (pin "19") (pinfunction "19_19") (pintype "bidirectional"))
      (node (ref "J1") (pin "20") (pinfunction "20_20") (pintype "bidirectional"))
      (node (ref "J1") (pin "4") (pinfunction "4_4") (pintype "bidirectional"))
      (node (ref "J1") (pin "6") (pinfunction "6_6") (pintype "bidirectional"))
      (node (ref "L14") (pin "1") (pinfunction "1_1") (pintype "passive"))
      (node (ref "R121") (pin "2") (pinfunction "2_2") (pintype "passive"))
      (node (ref "R178") (pin "2") (pinfunction "2_2") (pintype "passive"))
      (node (ref "R60") (pin "2") (pinfunction "2_2") (pintype "passive"))
      (node (ref "T3") (pin "5") (pinfunction "D_5") (pintype "passive"))
      (node (ref "T3") (pin "6") (pinfunction "D_6") (pintype "passive"))
      (node (ref "T4") (pin "5") (pinfunction "D_5") (pintype "passive"))
      (node (ref "T4") (pin "6") (pinfunction "D_6") (pintype "passive"))
      (node (ref "T7") (pin "5") (pinfunction "D_5") (pintype "passive"))
      (node (ref "T7") (pin "6") (pinfunction "D_6") (pintype "passive"))
      (node (ref "T9") (pin "5") (pinfunction "D_5") (pintype "passive"))
      (node (ref "T9") (pin "6") (pinfunction "D_6") (pintype "passive"))
    )
    (net (code "62") (name "P12V") (class "Default")
      (node (ref "B5") (pin "1") (pinfunction "1_1") (pintype "bidirectional"))
      (node (ref "C175") (pin "1") (pinfunction "1_1") (pintype "passive"))
      (node (ref "C435") (pin "1") (pinfunction "1_1") (pintype "passive"))
      (node (ref "D1") (pin "3") (pinfunction "C_3") (pintype "passive"))
      (node (ref "F1") (pin "1") (pinfunction "1_1") (pintype "passive"))
      (node (ref "R183") (pin "2") (pinfunction "2_2") (pintype "passive"))
    )
    (net (code "63") (name "P12V_FMC1") (class "Default")
      (node (ref "C241") (pin "1") (pinfunction "1_1") (pintype "passive"))
      (node (ref "C412") (pin "1") (pinfunction "1_1") (pintype "passive"))
      (node (ref "F1") (pin "2") (pinfunction "2_2") (pintype "passive"))
    )
    (net (code "64") (name "VREF_DDR3") (class "Default")
      (node (ref "C68") (pin "2") (pinfunction "2_2") (pintype "passive"))
      (node (ref "IC8") (pin "6") (pinfunction "REFOUT_6") (pintype "output"))
    )
    (net (code "65") (name "VTT_DDR3") (class "Default")
      (node (ref "C180") (pin "2") (pinfunction "2_2") (pintype "passive"))
      (node (ref "C62") (pin "2") (pinfunction "2_2") (pintype "passive"))
      (node (ref "IC8") (pin "3") (pinfunction "VO_3") (pintype "power_in"))
      (node (ref "IC8") (pin "5") (pinfunction "VOSNS_5") (pintype "input"))
    )
    (net (code "66") (name "unconnected-(J1-Pad9)") (class "Default")
      (node (ref "J1") (pin "9") (pinfunction "9_9") (pintype "bidirectional"))
    )
    (net (code "67") (name "unconnected-(J1-Pad10)") (class "Default")
      (node (ref "J1") (pin "10") (pinfunction "10_10") (pintype "bidirectional"))
    )
    (net (code "68") (name "unconnected-(J1-Pad12)") (class "Default")
      (node (ref "J1") (pin "12") (pinfunction "12_12") (pintype "bidirectional"))
    )
    (net (code "69") (name "unconnected-(J1-Pad18)") (class "Default")
      (node (ref "J1") (pin "18") (pinfunction "18_18") (pintype "bidirectional"))
    )
  )
)
